# MN42_v2a.net
KiCad netlist of a schematic drawn in EasyEDA Pro
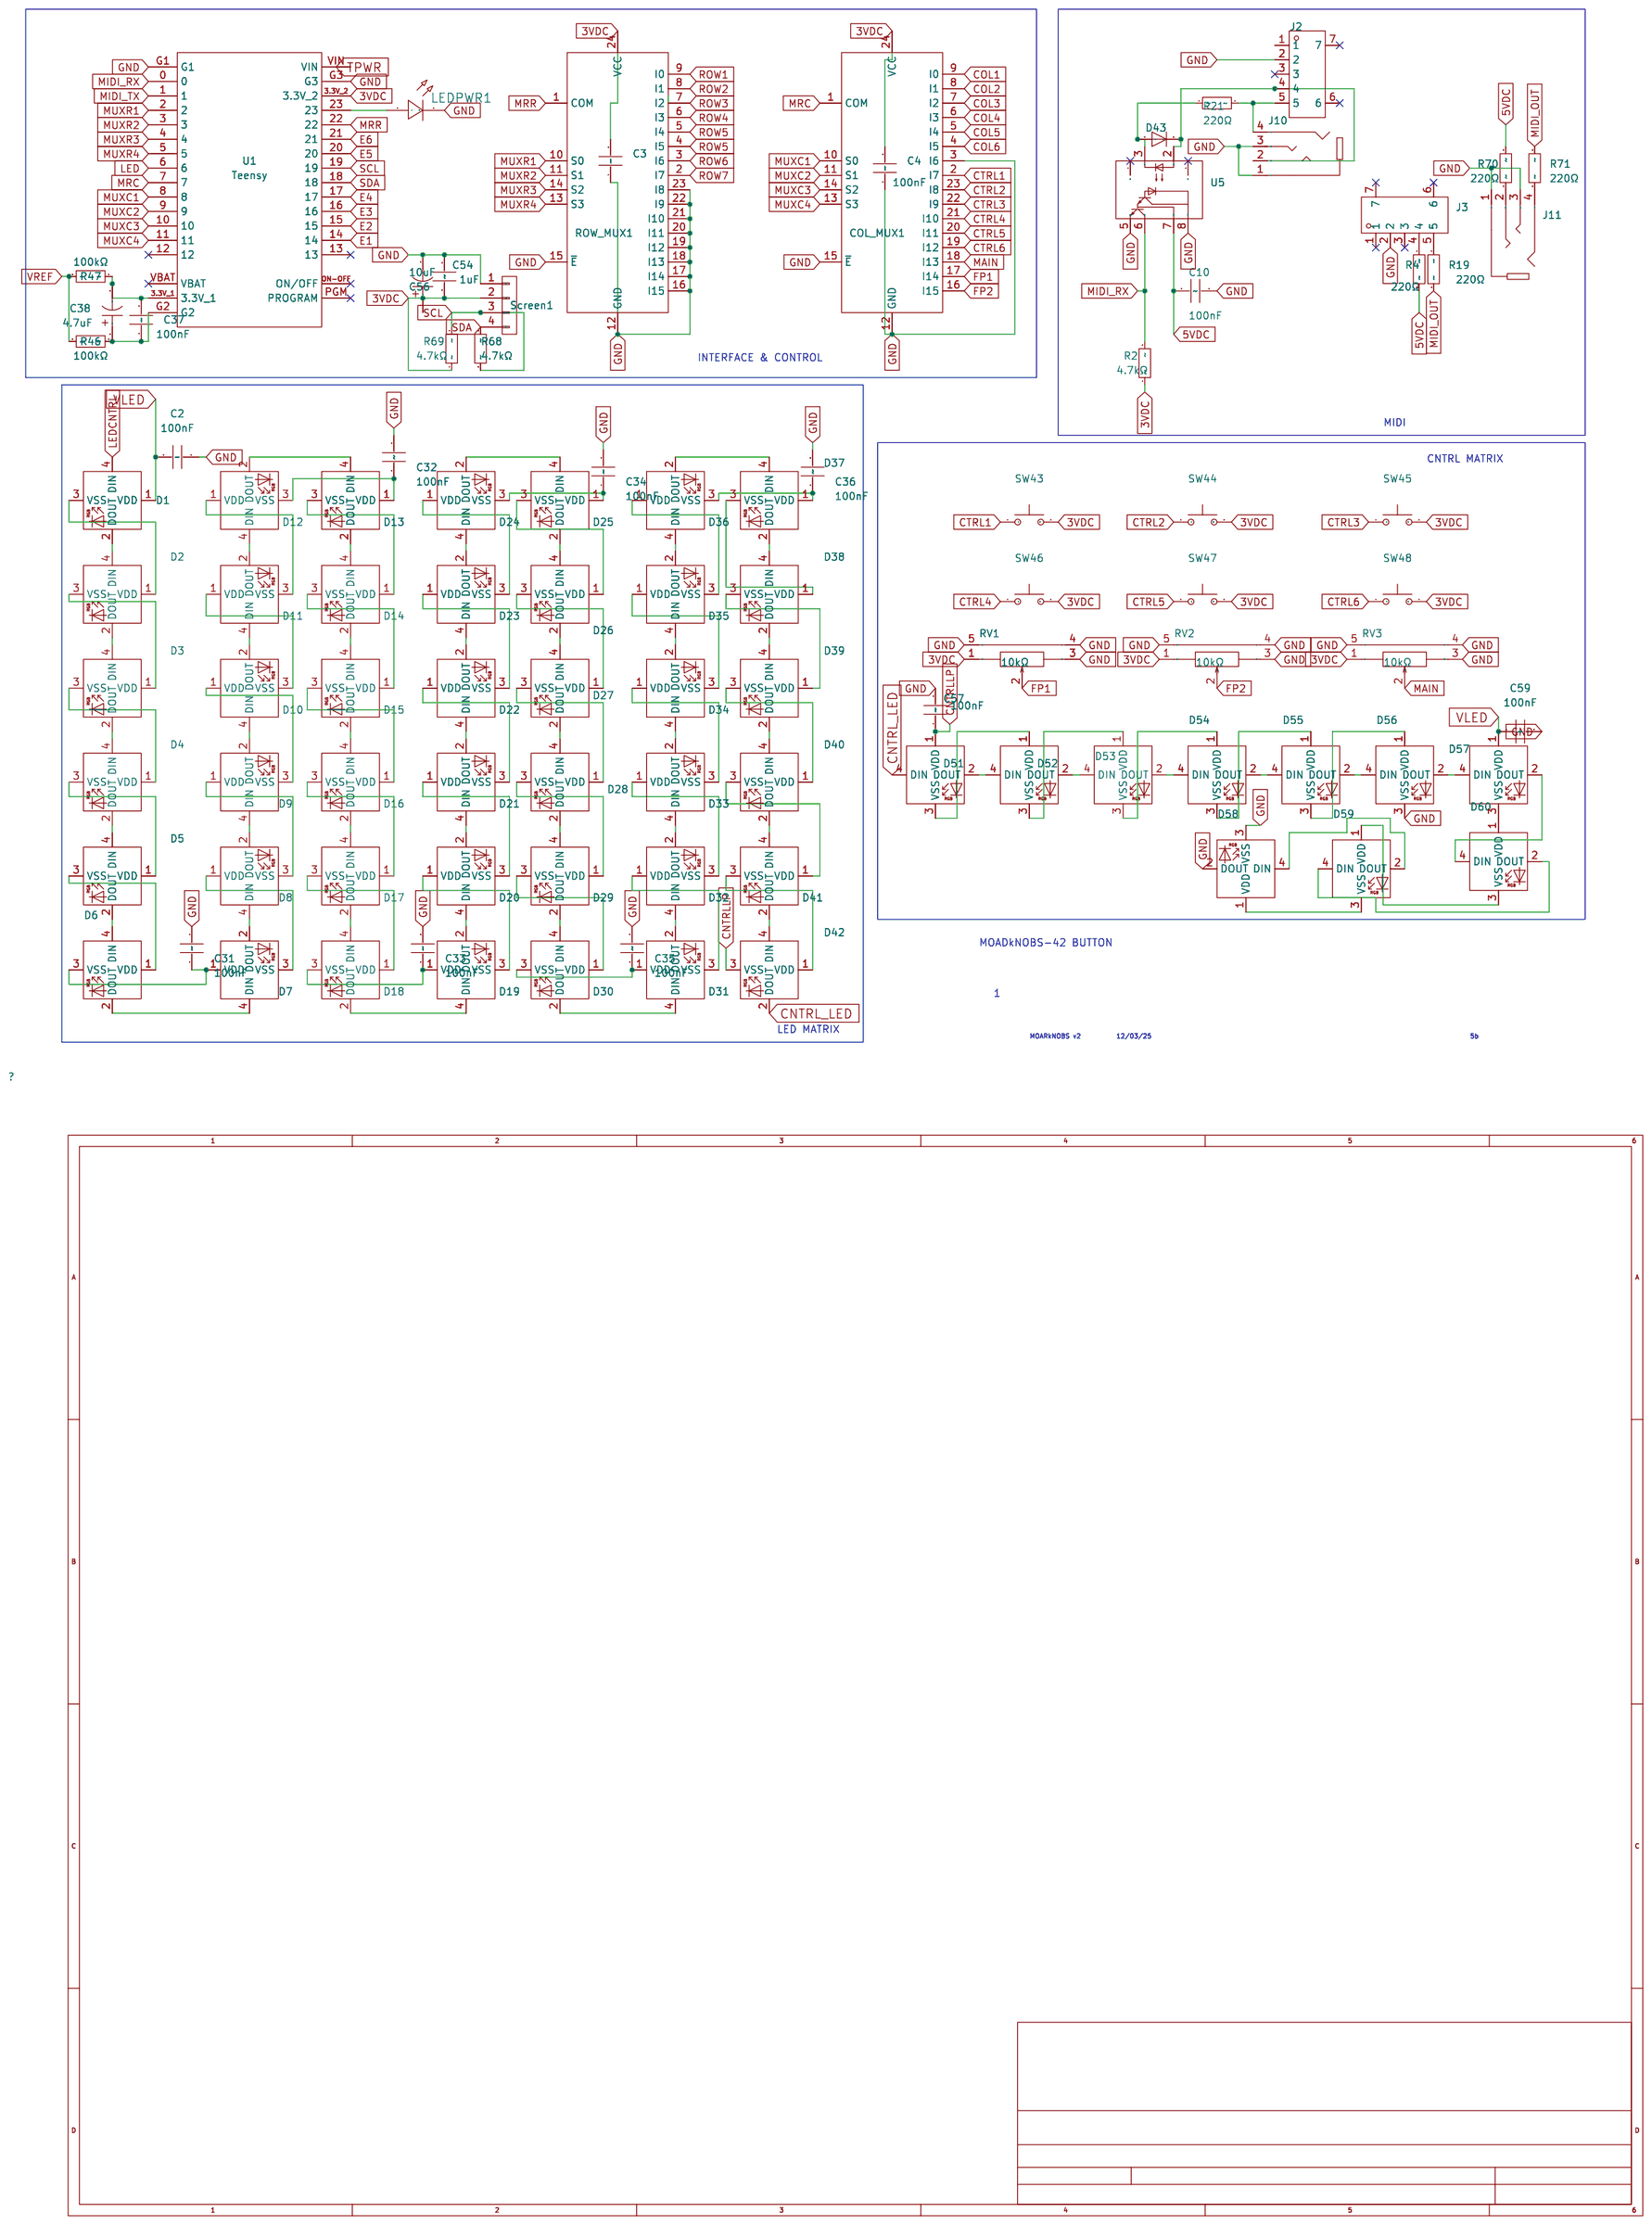
[diagram p0: INTERFACE/LED/MIDI/CNTRL]
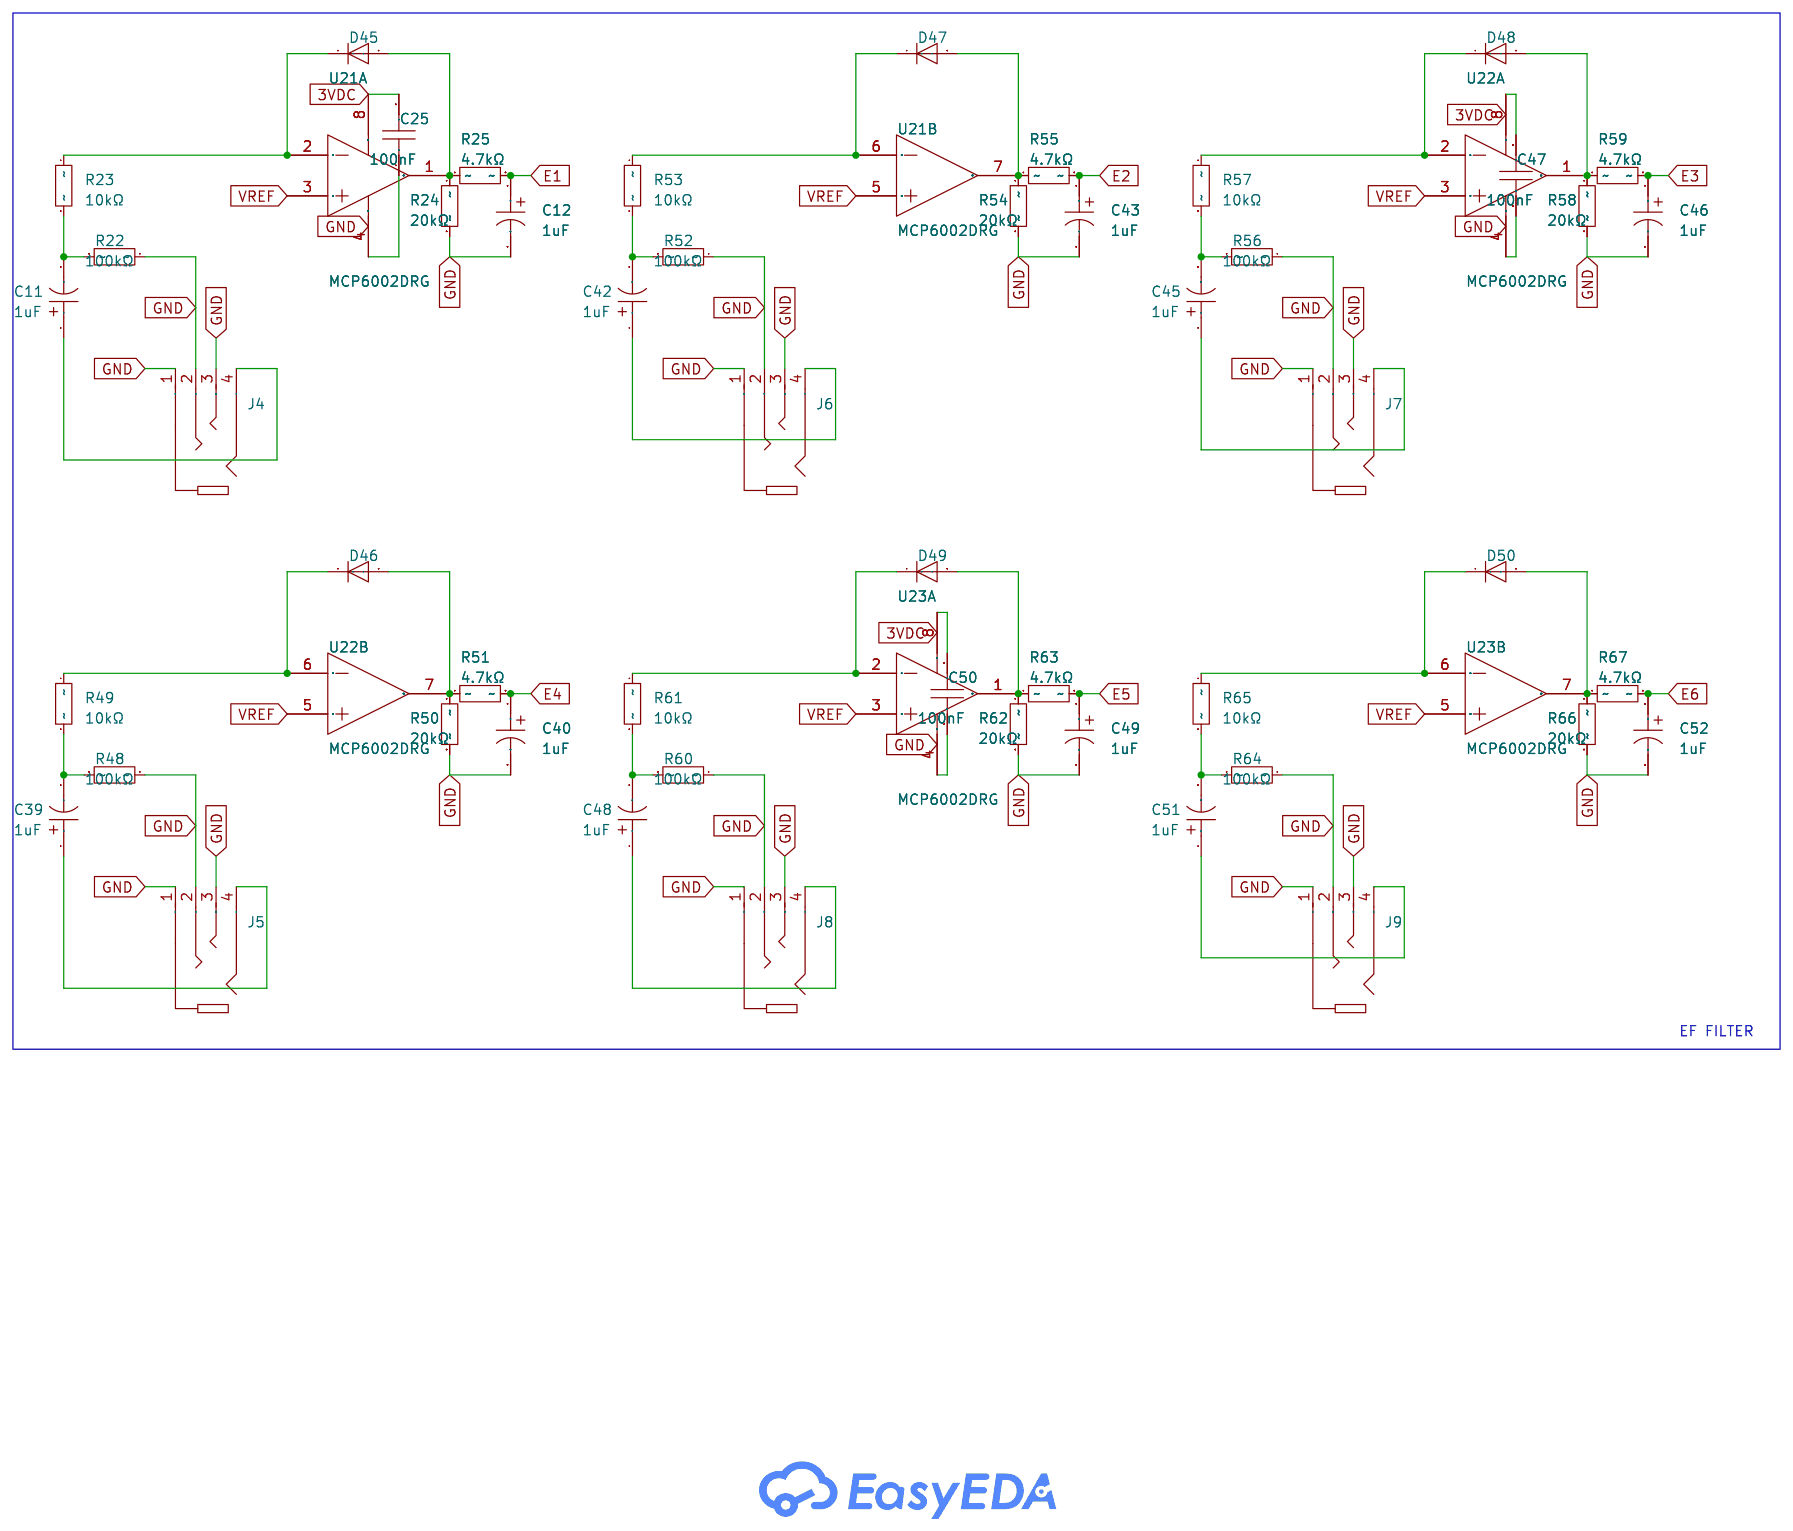
[diagram p1: ENVELOPE]
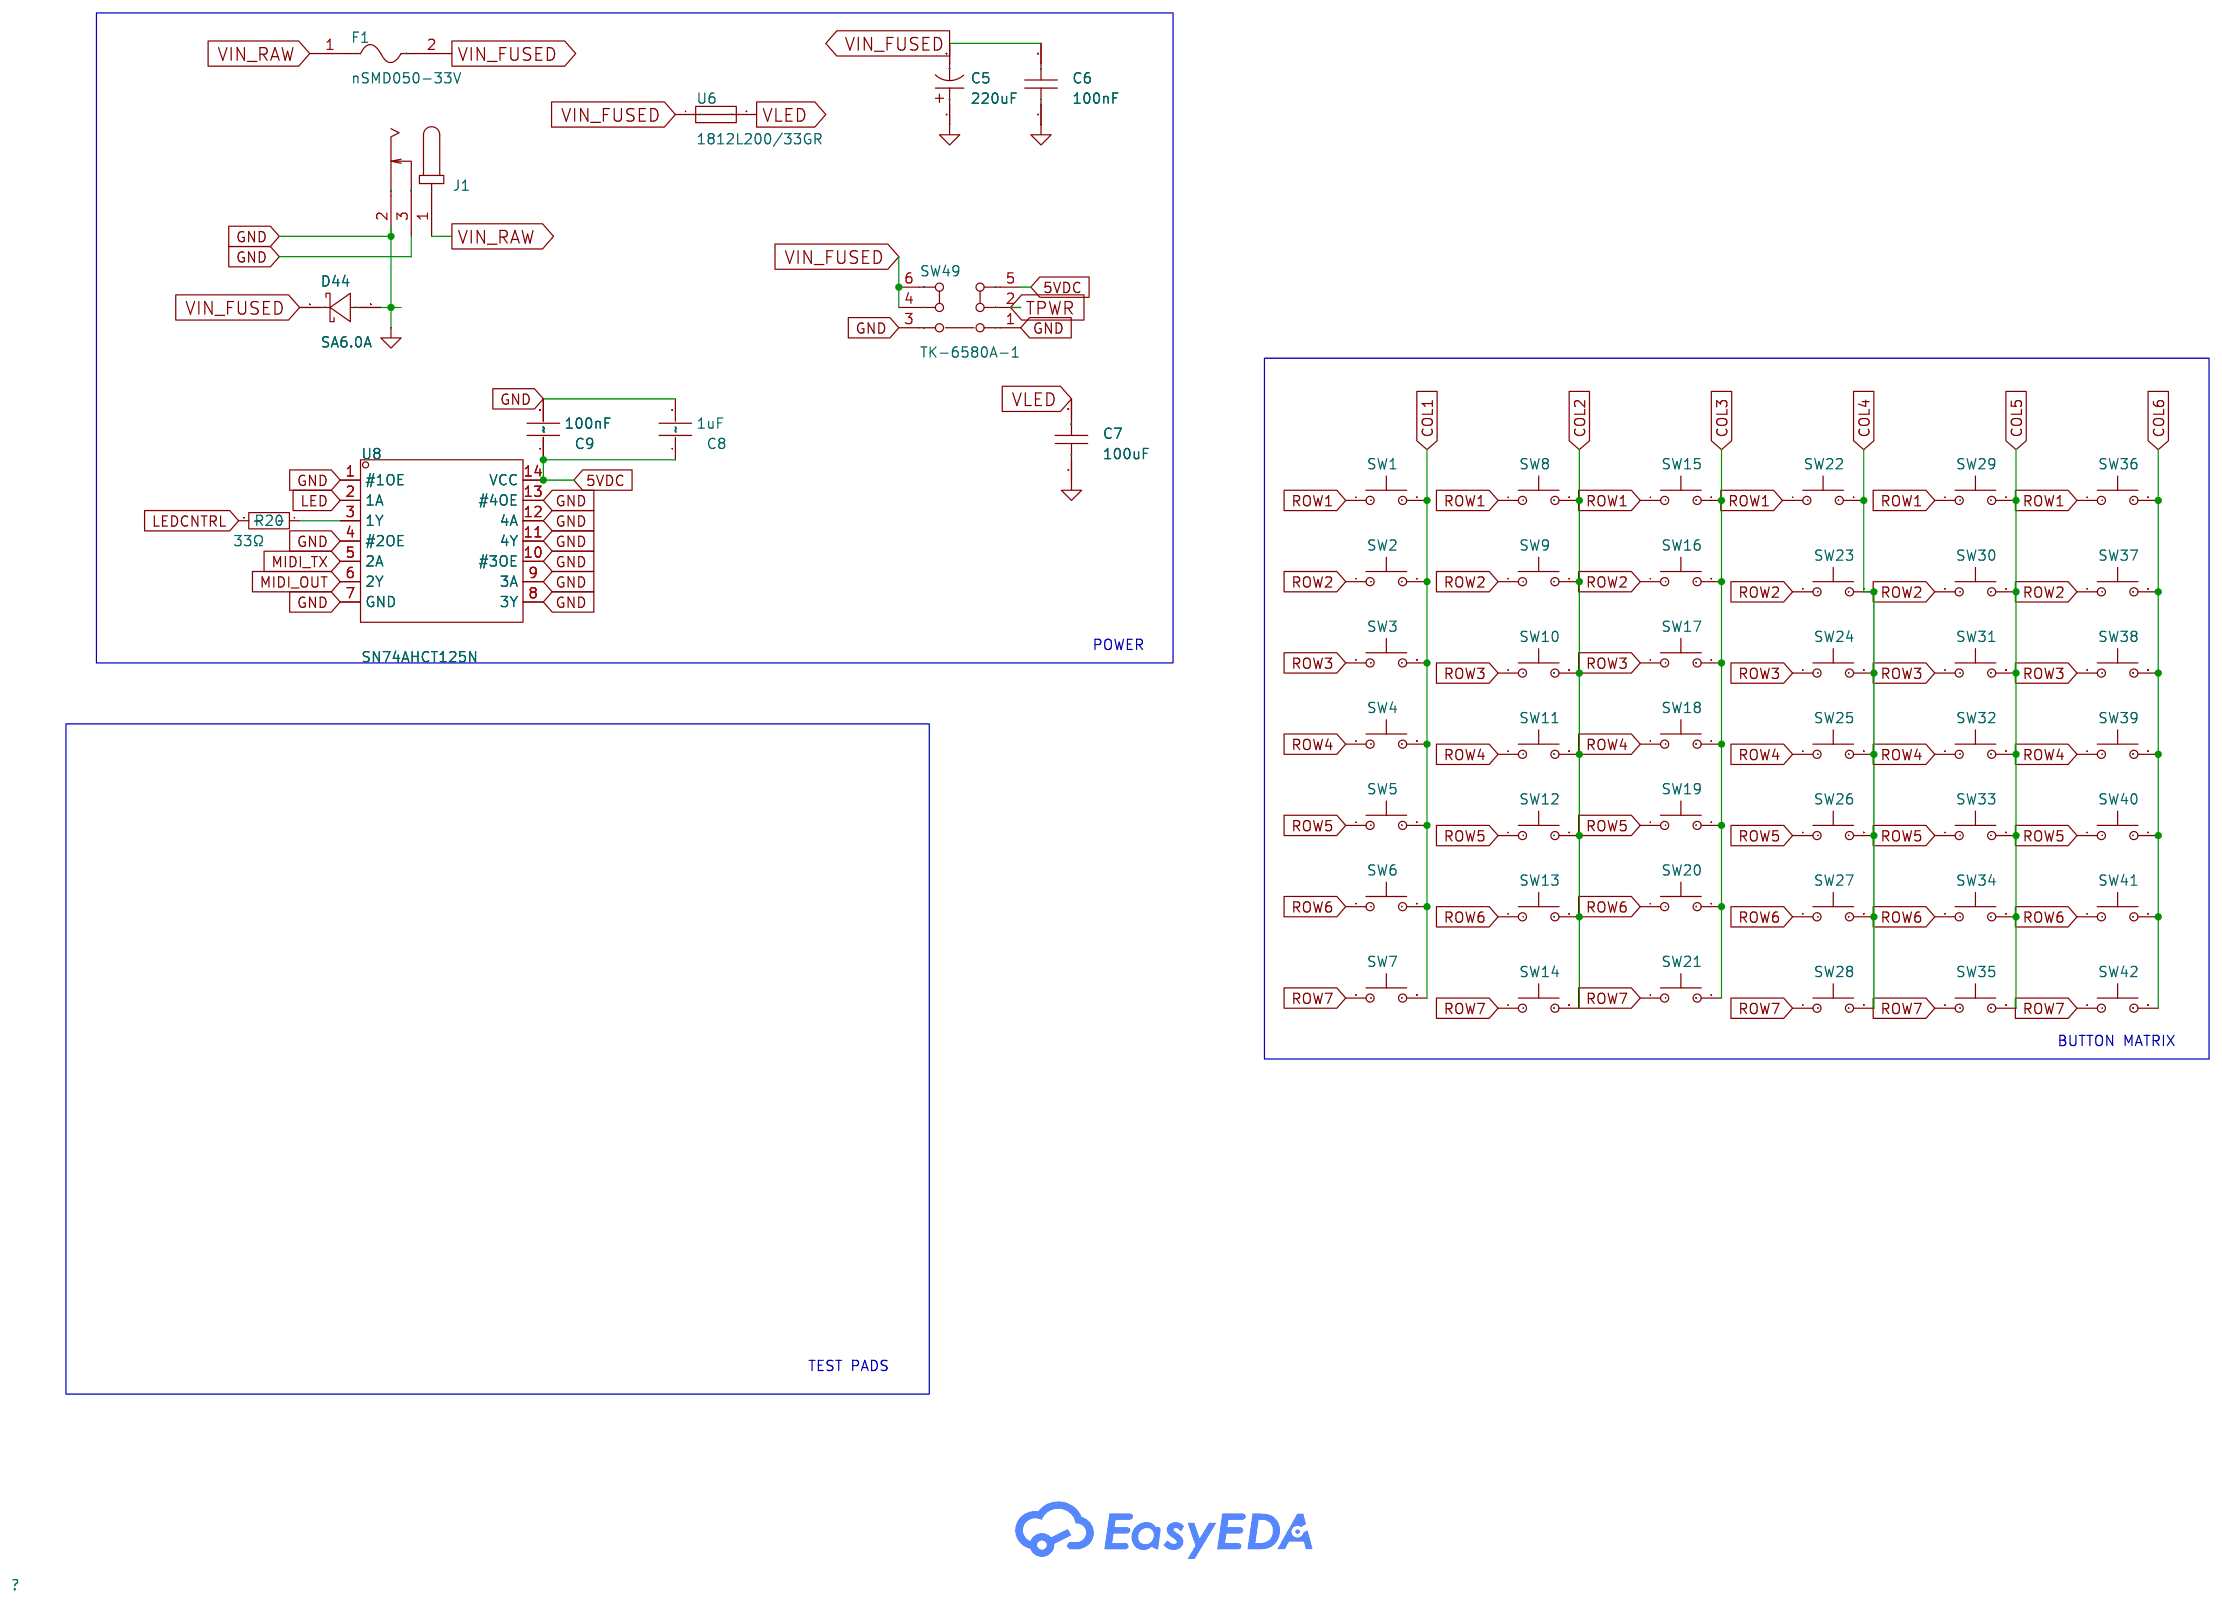
[diagram p2: PWR/BUTTON/TEST]

(export (version "E")
  (design (tool "Eeschema 10.0.6"))
  (components
    (comp (ref "C2")
      (value "100nF")
      (footprint "easyedapro:Capacitor_THT:C_Disc_D3.4mm_W2.1mm_P2.50mm")
      (description "Capacitance:100nF Tolerance:±10% Tolerance:±10% Voltage Rating:63V Temperature Coefficient:-")
      (fields
        (field (name "Manufacturer Part") "CT4G-0805-2X1-63V-0.1μF-K")
        (field (name "Manufacturer") "TORCH(火炬)")
      )
      (libsource (lib "easyedapro") (part "Device_C"))
    )
    (comp (ref "C3")
      (value "100nF")
      (footprint "easyedapro:Capacitor_THT:C_Disc_D3.4mm_W2.1mm_P2.50mm")
      (description "Capacitance:100nF Tolerance:±10% Tolerance:±10% Voltage Rating:63V Temperature Coefficient:-")
      (fields
        (field (name "Manufacturer Part") "CT4G-0805-2X1-63V-0.1μF-K")
        (field (name "Manufacturer") "TORCH(火炬)")
      )
      (libsource (lib "easyedapro") (part "Device_C"))
    )
    (comp (ref "C4")
      (value "100nF")
      (footprint "easyedapro:Capacitor_THT:C_Disc_D3.4mm_W2.1mm_P2.50mm")
      (description "Capacitance:100nF Tolerance:±10% Tolerance:±10% Voltage Rating:63V Temperature Coefficient:-")
      (fields
        (field (name "Manufacturer Part") "CT4G-0805-2X1-63V-0.1μF-K")
        (field (name "Manufacturer") "TORCH(火炬)")
      )
      (libsource (lib "easyedapro") (part "Device_C"))
    )
    (comp (ref "C10")
      (value "100nF")
      (footprint "easyedapro:Capacitor_THT:C_Disc_D3.4mm_W2.1mm_P2.50mm")
      (description "Capacitance:100nF Tolerance:±10% Tolerance:±10% Voltage Rating:63V Temperature Coefficient:-")
      (fields
        (field (name "Manufacturer Part") "CT4G-0805-2X1-63V-0.1μF-K")
        (field (name "Manufacturer") "TORCH(火炬)")
      )
      (libsource (lib "easyedapro") (part "Device_C"))
    )
    (comp (ref "C31")
      (value "100nF")
      (footprint "easyedapro:Capacitor_THT:C_Disc_D3.4mm_W2.1mm_P2.50mm")
      (description "Capacitance:100nF Tolerance:±10% Tolerance:±10% Voltage Rating:63V Temperature Coefficient:-")
      (fields
        (field (name "Manufacturer Part") "CT4G-0805-2X1-63V-0.1μF-K")
        (field (name "Manufacturer") "TORCH(火炬)")
      )
      (libsource (lib "easyedapro") (part "Device_C"))
    )
    (comp (ref "C32")
      (value "100nF")
      (footprint "easyedapro:Capacitor_THT:C_Disc_D3.4mm_W2.1mm_P2.50mm")
      (description "Capacitance:100nF Tolerance:±10% Tolerance:±10% Voltage Rating:63V Temperature Coefficient:-")
      (fields
        (field (name "Manufacturer Part") "CT4G-0805-2X1-63V-0.1μF-K")
        (field (name "Manufacturer") "TORCH(火炬)")
      )
      (libsource (lib "easyedapro") (part "Device_C"))
    )
    (comp (ref "C33")
      (value "100nF")
      (footprint "easyedapro:Capacitor_THT:C_Disc_D3.4mm_W2.1mm_P2.50mm")
      (description "Capacitance:100nF Tolerance:±10% Tolerance:±10% Voltage Rating:63V Temperature Coefficient:-")
      (fields
        (field (name "Manufacturer Part") "CT4G-0805-2X1-63V-0.1μF-K")
        (field (name "Manufacturer") "TORCH(火炬)")
      )
      (libsource (lib "easyedapro") (part "Device_C"))
    )
    (comp (ref "C34")
      (value "100nF")
      (footprint "easyedapro:Capacitor_THT:C_Disc_D3.4mm_W2.1mm_P2.50mm")
      (description "Capacitance:100nF Tolerance:±10% Tolerance:±10% Voltage Rating:63V Temperature Coefficient:-")
      (fields
        (field (name "Manufacturer Part") "CT4G-0805-2X1-63V-0.1μF-K")
        (field (name "Manufacturer") "TORCH(火炬)")
      )
      (libsource (lib "easyedapro") (part "Device_C"))
    )
    (comp (ref "C35")
      (value "100nF")
      (footprint "easyedapro:Capacitor_THT:C_Disc_D3.4mm_W2.1mm_P2.50mm")
      (description "Capacitance:100nF Tolerance:±10% Tolerance:±10% Voltage Rating:63V Temperature Coefficient:-")
      (fields
        (field (name "Manufacturer Part") "CT4G-0805-2X1-63V-0.1μF-K")
        (field (name "Manufacturer") "TORCH(火炬)")
      )
      (libsource (lib "easyedapro") (part "Device_C"))
    )
    (comp (ref "C36")
      (value "100nF")
      (footprint "easyedapro:Capacitor_THT:C_Disc_D3.4mm_W2.1mm_P2.50mm")
      (description "Capacitance:100nF Tolerance:±10% Tolerance:±10% Voltage Rating:63V Temperature Coefficient:-")
      (fields
        (field (name "Manufacturer Part") "CT4G-0805-2X1-63V-0.1μF-K")
        (field (name "Manufacturer") "TORCH(火炬)")
      )
      (libsource (lib "easyedapro") (part "Device_C"))
    )
    (comp (ref "C37")
      (value "100nF")
      (footprint "easyedapro:Capacitor_THT:C_Disc_D3.4mm_W2.1mm_P2.50mm")
      (description "Capacitance:100nF Tolerance:±10% Tolerance:±10% Voltage Rating:63V Temperature Coefficient:-")
      (fields
        (field (name "Manufacturer Part") "CT4G-0805-2X1-63V-0.1μF-K")
        (field (name "Manufacturer") "TORCH(火炬)")
      )
      (libsource (lib "easyedapro") (part "Device_C"))
    )
    (comp (ref "C38")
      (value "4.7uF")
      (footprint "easyedapro:CAP-SMD_BD6.3-L6.6-W6.6-FD")
      (fields (field (name "Manufacturer Part") "189RV0019") (field (name "Manufacturer") "KNSCHA(科尼盛)"))
      (libsource (lib "easyedapro") (part "189RV0019"))
    )
    (comp (ref "C54")
      (value "1uF")
      (footprint "easyedapro:Capacitor_THT:C_Disc_D3.4mm_W2.1mm_P2.50mm")
      (description "Capacitance:100nF Tolerance:±10% Tolerance:±10% Voltage Rating:63V Temperature Coefficient:-")
      (fields
        (field (name "Manufacturer Part") "CT4G-0805-2X1-63V-0.1μF-K")
        (field (name "Manufacturer") "TORCH(火炬)")
      )
      (libsource (lib "easyedapro") (part "Device_C"))
    )
    (comp (ref "C56")
      (value "10uF")
      (footprint "easyedapro:CAP-SMD_BD6.3-L6.6-W6.6-FD")
      (fields (field (name "Manufacturer Part") "189RV0019") (field (name "Manufacturer") "KNSCHA(科尼盛)"))
      (libsource (lib "easyedapro") (part "189RV0019"))
    )
    (comp (ref "C57")
      (value "100nF")
      (footprint "easyedapro:Capacitor_THT:C_Disc_D3.4mm_W2.1mm_P2.50mm")
      (description "Capacitance:100nF Tolerance:±10% Tolerance:±10% Voltage Rating:63V Temperature Coefficient:-")
      (fields
        (field (name "Manufacturer Part") "CT4G-0805-2X1-63V-0.1μF-K")
        (field (name "Manufacturer") "TORCH(火炬)")
      )
      (libsource (lib "easyedapro") (part "Device_C"))
    )
    (comp (ref "C59")
      (value "100nF")
      (footprint "easyedapro:Capacitor_THT:C_Disc_D3.4mm_W2.1mm_P2.50mm")
      (description "Capacitance:100nF Tolerance:±10% Tolerance:±10% Voltage Rating:63V Temperature Coefficient:-")
      (fields
        (field (name "Manufacturer Part") "CT4G-0805-2X1-63V-0.1μF-K")
        (field (name "Manufacturer") "TORCH(火炬)")
      )
      (libsource (lib "easyedapro") (part "Device_C"))
    )
    (comp (ref "COL_MUX1")
      (value "CD74HC4067M96")
      (footprint "easyedapro:Package_SO:SOIC-24W_7.5x15.4mm_P1.27mm")
      (fields (field (name "Manufacturer") "TI(德州仪器)"))
      (libsource (lib "easyedapro") (part "74xx_CD74HC4067M"))
    )
    (comp (ref "D1")
      (value "XL-5050RGBC-WS2812B")
      (footprint "easyedapro:LED_SMD:LED_WS2812B_PLCC4_5.0x5.0mm_P3.2mm")
      (fields (field (name "Manufacturer") "XINGLIGHT(成兴光)"))
      (libsource (lib "easyedapro") (part "LED_WS2812B"))
    )
    (comp (ref "D2")
      (value "XL-5050RGBC-WS2812B")
      (footprint "easyedapro:LED_SMD:LED_WS2812B_PLCC4_5.0x5.0mm_P3.2mm")
      (fields (field (name "Manufacturer") "XINGLIGHT(成兴光)"))
      (libsource (lib "easyedapro") (part "LED_WS2812B"))
    )
    (comp (ref "D3")
      (value "XL-5050RGBC-WS2812B")
      (footprint "easyedapro:LED_SMD:LED_WS2812B_PLCC4_5.0x5.0mm_P3.2mm")
      (fields (field (name "Manufacturer") "XINGLIGHT(成兴光)"))
      (libsource (lib "easyedapro") (part "LED_WS2812B"))
    )
    (comp (ref "D4")
      (value "XL-5050RGBC-WS2812B")
      (footprint "easyedapro:LED_SMD:LED_WS2812B_PLCC4_5.0x5.0mm_P3.2mm")
      (fields (field (name "Manufacturer") "XINGLIGHT(成兴光)"))
      (libsource (lib "easyedapro") (part "LED_WS2812B"))
    )
    (comp (ref "D5")
      (value "XL-5050RGBC-WS2812B")
      (footprint "easyedapro:LED_SMD:LED_WS2812B_PLCC4_5.0x5.0mm_P3.2mm")
      (fields (field (name "Manufacturer") "XINGLIGHT(成兴光)"))
      (libsource (lib "easyedapro") (part "LED_WS2812B"))
    )
    (comp (ref "D6")
      (value "XL-5050RGBC-WS2812B")
      (footprint "easyedapro:LED_SMD:LED_WS2812B_PLCC4_5.0x5.0mm_P3.2mm")
      (fields (field (name "Manufacturer") "XINGLIGHT(成兴光)"))
      (libsource (lib "easyedapro") (part "LED_WS2812B"))
    )
    (comp (ref "D7")
      (value "XL-5050RGBC-WS2812B")
      (footprint "easyedapro:LED_SMD:LED_WS2812B_PLCC4_5.0x5.0mm_P3.2mm")
      (fields (field (name "Manufacturer") "XINGLIGHT(成兴光)"))
      (libsource (lib "easyedapro") (part "LED_WS2812B"))
    )
    (comp (ref "D8")
      (value "XL-5050RGBC-WS2812B")
      (footprint "easyedapro:LED_SMD:LED_WS2812B_PLCC4_5.0x5.0mm_P3.2mm")
      (fields (field (name "Manufacturer") "XINGLIGHT(成兴光)"))
      (libsource (lib "easyedapro") (part "LED_WS2812B"))
    )
    (comp (ref "D9")
      (value "XL-5050RGBC-WS2812B")
      (footprint "easyedapro:LED_SMD:LED_WS2812B_PLCC4_5.0x5.0mm_P3.2mm")
      (fields (field (name "Manufacturer") "XINGLIGHT(成兴光)"))
      (libsource (lib "easyedapro") (part "LED_WS2812B"))
    )
    (comp (ref "D10")
      (value "XL-5050RGBC-WS2812B")
      (footprint "easyedapro:LED_SMD:LED_WS2812B_PLCC4_5.0x5.0mm_P3.2mm")
      (fields (field (name "Manufacturer") "XINGLIGHT(成兴光)"))
      (libsource (lib "easyedapro") (part "LED_WS2812B"))
    )
    (comp (ref "D11")
      (value "XL-5050RGBC-WS2812B")
      (footprint "easyedapro:LED_SMD:LED_WS2812B_PLCC4_5.0x5.0mm_P3.2mm")
      (fields (field (name "Manufacturer") "XINGLIGHT(成兴光)"))
      (libsource (lib "easyedapro") (part "LED_WS2812B"))
    )
    (comp (ref "D12")
      (value "XL-5050RGBC-WS2812B")
      (footprint "easyedapro:LED_SMD:LED_WS2812B_PLCC4_5.0x5.0mm_P3.2mm")
      (fields (field (name "Manufacturer") "XINGLIGHT(成兴光)"))
      (libsource (lib "easyedapro") (part "LED_WS2812B"))
    )
    (comp (ref "D13")
      (value "XL-5050RGBC-WS2812B")
      (footprint "easyedapro:LED_SMD:LED_WS2812B_PLCC4_5.0x5.0mm_P3.2mm")
      (fields (field (name "Manufacturer") "XINGLIGHT(成兴光)"))
      (libsource (lib "easyedapro") (part "LED_WS2812B"))
    )
    (comp (ref "D14")
      (value "XL-5050RGBC-WS2812B")
      (footprint "easyedapro:LED_SMD:LED_WS2812B_PLCC4_5.0x5.0mm_P3.2mm")
      (fields (field (name "Manufacturer") "XINGLIGHT(成兴光)"))
      (libsource (lib "easyedapro") (part "LED_WS2812B"))
    )
    (comp (ref "D15")
      (value "XL-5050RGBC-WS2812B")
      (footprint "easyedapro:LED_SMD:LED_WS2812B_PLCC4_5.0x5.0mm_P3.2mm")
      (fields (field (name "Manufacturer") "XINGLIGHT(成兴光)"))
      (libsource (lib "easyedapro") (part "LED_WS2812B"))
    )
    (comp (ref "D16")
      (value "XL-5050RGBC-WS2812B")
      (footprint "easyedapro:LED_SMD:LED_WS2812B_PLCC4_5.0x5.0mm_P3.2mm")
      (fields (field (name "Manufacturer") "XINGLIGHT(成兴光)"))
      (libsource (lib "easyedapro") (part "LED_WS2812B"))
    )
    (comp (ref "D17")
      (value "XL-5050RGBC-WS2812B")
      (footprint "easyedapro:LED_SMD:LED_WS2812B_PLCC4_5.0x5.0mm_P3.2mm")
      (fields (field (name "Manufacturer") "XINGLIGHT(成兴光)"))
      (libsource (lib "easyedapro") (part "LED_WS2812B"))
    )
    (comp (ref "D18")
      (value "XL-5050RGBC-WS2812B")
      (footprint "easyedapro:LED_SMD:LED_WS2812B_PLCC4_5.0x5.0mm_P3.2mm")
      (fields (field (name "Manufacturer") "XINGLIGHT(成兴光)"))
      (libsource (lib "easyedapro") (part "LED_WS2812B"))
    )
    (comp (ref "D19")
      (value "XL-5050RGBC-WS2812B")
      (footprint "easyedapro:LED_SMD:LED_WS2812B_PLCC4_5.0x5.0mm_P3.2mm")
      (fields (field (name "Manufacturer") "XINGLIGHT(成兴光)"))
      (libsource (lib "easyedapro") (part "LED_WS2812B"))
    )
    (comp (ref "D20")
      (value "XL-5050RGBC-WS2812B")
      (footprint "easyedapro:LED_SMD:LED_WS2812B_PLCC4_5.0x5.0mm_P3.2mm")
      (fields (field (name "Manufacturer") "XINGLIGHT(成兴光)"))
      (libsource (lib "easyedapro") (part "LED_WS2812B"))
    )
    (comp (ref "D21")
      (value "XL-5050RGBC-WS2812B")
      (footprint "easyedapro:LED_SMD:LED_WS2812B_PLCC4_5.0x5.0mm_P3.2mm")
      (fields (field (name "Manufacturer") "XINGLIGHT(成兴光)"))
      (libsource (lib "easyedapro") (part "LED_WS2812B"))
    )
    (comp (ref "D22")
      (value "XL-5050RGBC-WS2812B")
      (footprint "easyedapro:LED_SMD:LED_WS2812B_PLCC4_5.0x5.0mm_P3.2mm")
      (fields (field (name "Manufacturer") "XINGLIGHT(成兴光)"))
      (libsource (lib "easyedapro") (part "LED_WS2812B"))
    )
    (comp (ref "D23")
      (value "XL-5050RGBC-WS2812B")
      (footprint "easyedapro:LED_SMD:LED_WS2812B_PLCC4_5.0x5.0mm_P3.2mm")
      (fields (field (name "Manufacturer") "XINGLIGHT(成兴光)"))
      (libsource (lib "easyedapro") (part "LED_WS2812B"))
    )
    (comp (ref "D24")
      (value "XL-5050RGBC-WS2812B")
      (footprint "easyedapro:LED_SMD:LED_WS2812B_PLCC4_5.0x5.0mm_P3.2mm")
      (fields (field (name "Manufacturer") "XINGLIGHT(成兴光)"))
      (libsource (lib "easyedapro") (part "LED_WS2812B"))
    )
    (comp (ref "D25")
      (value "XL-5050RGBC-WS2812B")
      (footprint "easyedapro:LED_SMD:LED_WS2812B_PLCC4_5.0x5.0mm_P3.2mm")
      (fields (field (name "Manufacturer") "XINGLIGHT(成兴光)"))
      (libsource (lib "easyedapro") (part "LED_WS2812B"))
    )
    (comp (ref "D26")
      (value "XL-5050RGBC-WS2812B")
      (footprint "easyedapro:LED_SMD:LED_WS2812B_PLCC4_5.0x5.0mm_P3.2mm")
      (fields (field (name "Manufacturer") "XINGLIGHT(成兴光)"))
      (libsource (lib "easyedapro") (part "LED_WS2812B"))
    )
    (comp (ref "D27")
      (value "XL-5050RGBC-WS2812B")
      (footprint "easyedapro:LED_SMD:LED_WS2812B_PLCC4_5.0x5.0mm_P3.2mm")
      (fields (field (name "Manufacturer") "XINGLIGHT(成兴光)"))
      (libsource (lib "easyedapro") (part "LED_WS2812B"))
    )
    (comp (ref "D28")
      (value "XL-5050RGBC-WS2812B")
      (footprint "easyedapro:LED_SMD:LED_WS2812B_PLCC4_5.0x5.0mm_P3.2mm")
      (fields (field (name "Manufacturer") "XINGLIGHT(成兴光)"))
      (libsource (lib "easyedapro") (part "LED_WS2812B"))
    )
    (comp (ref "D29")
      (value "XL-5050RGBC-WS2812B")
      (footprint "easyedapro:LED_SMD:LED_WS2812B_PLCC4_5.0x5.0mm_P3.2mm")
      (fields (field (name "Manufacturer") "XINGLIGHT(成兴光)"))
      (libsource (lib "easyedapro") (part "LED_WS2812B"))
    )
    (comp (ref "D30")
      (value "XL-5050RGBC-WS2812B")
      (footprint "easyedapro:LED_SMD:LED_WS2812B_PLCC4_5.0x5.0mm_P3.2mm")
      (fields (field (name "Manufacturer") "XINGLIGHT(成兴光)"))
      (libsource (lib "easyedapro") (part "LED_WS2812B"))
    )
    (comp (ref "D31")
      (value "XL-5050RGBC-WS2812B")
      (footprint "easyedapro:LED_SMD:LED_WS2812B_PLCC4_5.0x5.0mm_P3.2mm")
      (fields (field (name "Manufacturer") "XINGLIGHT(成兴光)"))
      (libsource (lib "easyedapro") (part "LED_WS2812B"))
    )
    (comp (ref "D32")
      (value "XL-5050RGBC-WS2812B")
      (footprint "easyedapro:LED_SMD:LED_WS2812B_PLCC4_5.0x5.0mm_P3.2mm")
      (fields (field (name "Manufacturer") "XINGLIGHT(成兴光)"))
      (libsource (lib "easyedapro") (part "LED_WS2812B"))
    )
    (comp (ref "D33")
      (value "XL-5050RGBC-WS2812B")
      (footprint "easyedapro:LED_SMD:LED_WS2812B_PLCC4_5.0x5.0mm_P3.2mm")
      (fields (field (name "Manufacturer") "XINGLIGHT(成兴光)"))
      (libsource (lib "easyedapro") (part "LED_WS2812B"))
    )
    (comp (ref "D34")
      (value "XL-5050RGBC-WS2812B")
      (footprint "easyedapro:LED_SMD:LED_WS2812B_PLCC4_5.0x5.0mm_P3.2mm")
      (fields (field (name "Manufacturer") "XINGLIGHT(成兴光)"))
      (libsource (lib "easyedapro") (part "LED_WS2812B"))
    )
    (comp (ref "D35")
      (value "XL-5050RGBC-WS2812B")
      (footprint "easyedapro:LED_SMD:LED_WS2812B_PLCC4_5.0x5.0mm_P3.2mm")
      (fields (field (name "Manufacturer") "XINGLIGHT(成兴光)"))
      (libsource (lib "easyedapro") (part "LED_WS2812B"))
    )
    (comp (ref "D36")
      (value "XL-5050RGBC-WS2812B")
      (footprint "easyedapro:LED_SMD:LED_WS2812B_PLCC4_5.0x5.0mm_P3.2mm")
      (fields (field (name "Manufacturer") "XINGLIGHT(成兴光)"))
      (libsource (lib "easyedapro") (part "LED_WS2812B"))
    )
    (comp (ref "D37")
      (value "XL-5050RGBC-WS2812B")
      (footprint "easyedapro:LED_SMD:LED_WS2812B_PLCC4_5.0x5.0mm_P3.2mm")
      (fields (field (name "Manufacturer") "XINGLIGHT(成兴光)"))
      (libsource (lib "easyedapro") (part "LED_WS2812B"))
    )
    (comp (ref "D38")
      (value "XL-5050RGBC-WS2812B")
      (footprint "easyedapro:LED_SMD:LED_WS2812B_PLCC4_5.0x5.0mm_P3.2mm")
      (fields (field (name "Manufacturer") "XINGLIGHT(成兴光)"))
      (libsource (lib "easyedapro") (part "LED_WS2812B"))
    )
    (comp (ref "D39")
      (value "XL-5050RGBC-WS2812B")
      (footprint "easyedapro:LED_SMD:LED_WS2812B_PLCC4_5.0x5.0mm_P3.2mm")
      (fields (field (name "Manufacturer") "XINGLIGHT(成兴光)"))
      (libsource (lib "easyedapro") (part "LED_WS2812B"))
    )
    (comp (ref "D40")
      (value "XL-5050RGBC-WS2812B")
      (footprint "easyedapro:LED_SMD:LED_WS2812B_PLCC4_5.0x5.0mm_P3.2mm")
      (fields (field (name "Manufacturer") "XINGLIGHT(成兴光)"))
      (libsource (lib "easyedapro") (part "LED_WS2812B"))
    )
    (comp (ref "D41")
      (value "XL-5050RGBC-WS2812B")
      (footprint "easyedapro:LED_SMD:LED_WS2812B_PLCC4_5.0x5.0mm_P3.2mm")
      (fields (field (name "Manufacturer") "XINGLIGHT(成兴光)"))
      (libsource (lib "easyedapro") (part "LED_WS2812B"))
    )
    (comp (ref "D42")
      (value "XL-5050RGBC-WS2812B")
      (footprint "easyedapro:LED_SMD:LED_WS2812B_PLCC4_5.0x5.0mm_P3.2mm")
      (fields (field (name "Manufacturer") "XINGLIGHT(成兴光)"))
      (libsource (lib "easyedapro") (part "LED_WS2812B"))
    )
    (comp (ref "D43")
      (value "1N4148PF")
      (footprint "easyedapro:Diode_THT:D_DO-35_SOD27_P7.62mm_Horizontal")
      (fields (field (name "Manufacturer") "ST(先科)"))
      (libsource (lib "easyedapro") (part "Diode_1N4148"))
    )
    (comp (ref "D51")
      (value "XL-5050RGBC-WS2812B")
      (footprint "easyedapro:LED_SMD:LED_WS2812B_PLCC4_5.0x5.0mm_P3.2mm")
      (fields (field (name "Manufacturer") "XINGLIGHT(成兴光)"))
      (libsource (lib "easyedapro") (part "LED_WS2812B"))
    )
    (comp (ref "D52")
      (value "XL-5050RGBC-WS2812B")
      (footprint "easyedapro:LED_SMD:LED_WS2812B_PLCC4_5.0x5.0mm_P3.2mm")
      (fields (field (name "Manufacturer") "XINGLIGHT(成兴光)"))
      (libsource (lib "easyedapro") (part "LED_WS2812B"))
    )
    (comp (ref "D53")
      (value "XL-5050RGBC-WS2812B")
      (footprint "easyedapro:LED_SMD:LED_WS2812B_PLCC4_5.0x5.0mm_P3.2mm")
      (fields (field (name "Manufacturer") "XINGLIGHT(成兴光)"))
      (libsource (lib "easyedapro") (part "LED_WS2812B"))
    )
    (comp (ref "D54")
      (value "XL-5050RGBC-WS2812B")
      (footprint "easyedapro:LED_SMD:LED_WS2812B_PLCC4_5.0x5.0mm_P3.2mm")
      (fields (field (name "Manufacturer") "XINGLIGHT(成兴光)"))
      (libsource (lib "easyedapro") (part "LED_WS2812B"))
    )
    (comp (ref "D55")
      (value "XL-5050RGBC-WS2812B")
      (footprint "easyedapro:LED_SMD:LED_WS2812B_PLCC4_5.0x5.0mm_P3.2mm")
      (fields (field (name "Manufacturer") "XINGLIGHT(成兴光)"))
      (libsource (lib "easyedapro") (part "LED_WS2812B"))
    )
    (comp (ref "D56")
      (value "XL-5050RGBC-WS2812B")
      (footprint "easyedapro:LED_SMD:LED_WS2812B_PLCC4_5.0x5.0mm_P3.2mm")
      (fields (field (name "Manufacturer") "XINGLIGHT(成兴光)"))
      (libsource (lib "easyedapro") (part "LED_WS2812B"))
    )
    (comp (ref "D57")
      (value "XL-5050RGBC-WS2812B")
      (footprint "easyedapro:LED_SMD:LED_WS2812B_PLCC4_5.0x5.0mm_P3.2mm")
      (fields (field (name "Manufacturer") "XINGLIGHT(成兴光)"))
      (libsource (lib "easyedapro") (part "LED_WS2812B"))
    )
    (comp (ref "D58")
      (value "XL-5050RGBC-WS2812B")
      (footprint "easyedapro:LED_SMD:LED_WS2812B_PLCC4_5.0x5.0mm_P3.2mm")
      (fields (field (name "Manufacturer") "XINGLIGHT(成兴光)"))
      (libsource (lib "easyedapro") (part "LED_WS2812B"))
    )
    (comp (ref "D59")
      (value "XL-5050RGBC-WS2812B")
      (footprint "easyedapro:LED_SMD:LED_WS2812B_PLCC4_5.0x5.0mm_P3.2mm")
      (fields (field (name "Manufacturer") "XINGLIGHT(成兴光)"))
      (libsource (lib "easyedapro") (part "LED_WS2812B"))
    )
    (comp (ref "D60")
      (value "XL-5050RGBC-WS2812B")
      (footprint "easyedapro:LED_SMD:LED_WS2812B_PLCC4_5.0x5.0mm_P3.2mm")
      (fields (field (name "Manufacturer") "XINGLIGHT(成兴光)"))
      (libsource (lib "easyedapro") (part "LED_WS2812B"))
    )
    (comp (ref "J2")
      (value "DIN-504B-M10")
      (footprint "easyedapro:CONN-TH_DIN-504B-M10")
      (fields (field (name "Manufacturer") "HOOYA(皓宇电子)"))
      (libsource (lib "easyedapro") (part "DIN-504B-M10"))
    )
    (comp (ref "J3")
      (value "DIN-504B-M10")
      (footprint "easyedapro:CONN-TH_DIN-504B-M10")
      (fields (field (name "Manufacturer") "HOOYA(皓宇电子)"))
      (libsource (lib "easyedapro") (part "DIN-504B-M10"))
    )
    (comp (ref "J10")
      (value "HC-PJ-320A")
      (footprint "easyedapro:AUDIO-SMD_HC-PJ-320A")
      (fields (field (name "Manufacturer") "HC(虹成电子)"))
      (libsource (lib "easyedapro") (part "HC-PJ-320A"))
    )
    (comp (ref "J11")
      (value "HC-PJ-320A")
      (footprint "easyedapro:AUDIO-SMD_HC-PJ-320A")
      (fields (field (name "Manufacturer") "HC(虹成电子)"))
      (libsource (lib "easyedapro") (part "HC-PJ-320A"))
    )
    (comp (ref "LEDPWR1")
      (value "~")
      (footprint "easyedapro:LED_0603")
      (libsource (lib "easyedapro") (part "LED_R"))
    )
    (comp (ref "R2")
      (value "4.7kΩ")
      (footprint "easyedapro:Resistor_THT:R_Axial_DIN0204_L3.6mm_D1.6mm_P2.54mm_Vertical")
      (fields
        (field (name "Manufacturer Part") "RN 1/8W 4K7 F T/B A1")
        (field (name "Manufacturer") "Tyohm(幸亚电阻)")
      )
      (libsource (lib "easyedapro") (part "Device_R"))
    )
    (comp (ref "R4")
      (value "220Ω")
      (footprint "easyedapro:Resistor_THT:R_Axial_DIN0204_L3.6mm_D1.6mm_P2.54mm_Vertical")
      (fields
        (field (name "Manufacturer Part") "RN 1/8W 220R F T/B A1")
        (field (name "Manufacturer") "Tyohm(幸亚电阻)")
      )
      (libsource (lib "easyedapro") (part "Device_R"))
    )
    (comp (ref "R19")
      (value "220Ω")
      (footprint "easyedapro:Resistor_THT:R_Axial_DIN0204_L3.6mm_D1.6mm_P2.54mm_Vertical")
      (fields
        (field (name "Manufacturer Part") "RN 1/8W 220R F T/B A1")
        (field (name "Manufacturer") "Tyohm(幸亚电阻)")
      )
      (libsource (lib "easyedapro") (part "Device_R"))
    )
    (comp (ref "R21")
      (value "220Ω")
      (footprint "easyedapro:Resistor_THT:R_Axial_DIN0204_L3.6mm_D1.6mm_P2.54mm_Vertical")
      (fields
        (field (name "Manufacturer Part") "RN 1/8W 220R F T/B A1")
        (field (name "Manufacturer") "Tyohm(幸亚电阻)")
      )
      (libsource (lib "easyedapro") (part "Device_R"))
    )
    (comp (ref "R46")
      (value "100kΩ")
      (footprint "easyedapro:Resistor_THT:R_Axial_DIN0204_L3.6mm_D1.6mm_P2.54mm_Vertical")
      (fields
        (field (name "Manufacturer Part") "RN1/8W10KFT/BA1")
        (field (name "Manufacturer") "Tyohm(幸亚电阻)")
      )
      (libsource (lib "easyedapro") (part "Device_R"))
    )
    (comp (ref "R47")
      (value "100kΩ")
      (footprint "easyedapro:Resistor_THT:R_Axial_DIN0204_L3.6mm_D1.6mm_P2.54mm_Vertical")
      (fields
        (field (name "Manufacturer Part") "RN1/8W10KFT/BA1")
        (field (name "Manufacturer") "Tyohm(幸亚电阻)")
      )
      (libsource (lib "easyedapro") (part "Device_R"))
    )
    (comp (ref "R68")
      (value "4.7kΩ")
      (footprint "easyedapro:Resistor_THT:R_Axial_DIN0204_L3.6mm_D1.6mm_P2.54mm_Vertical")
      (fields
        (field (name "Manufacturer Part") "RN 1/8W 4K7 F T/B A1")
        (field (name "Manufacturer") "Tyohm(幸亚电阻)")
      )
      (libsource (lib "easyedapro") (part "Device_R"))
    )
    (comp (ref "R69")
      (value "4.7kΩ")
      (footprint "easyedapro:Resistor_THT:R_Axial_DIN0204_L3.6mm_D1.6mm_P2.54mm_Vertical")
      (fields
        (field (name "Manufacturer Part") "RN 1/8W 4K7 F T/B A1")
        (field (name "Manufacturer") "Tyohm(幸亚电阻)")
      )
      (libsource (lib "easyedapro") (part "Device_R"))
    )
    (comp (ref "R70")
      (value "220Ω")
      (footprint "easyedapro:Resistor_THT:R_Axial_DIN0204_L3.6mm_D1.6mm_P2.54mm_Vertical")
      (fields
        (field (name "Manufacturer Part") "RN 1/8W 220R F T/B A1")
        (field (name "Manufacturer") "Tyohm(幸亚电阻)")
      )
      (libsource (lib "easyedapro") (part "Device_R"))
    )
    (comp (ref "R71")
      (value "220Ω")
      (footprint "easyedapro:Resistor_THT:R_Axial_DIN0204_L3.6mm_D1.6mm_P2.54mm_Vertical")
      (fields
        (field (name "Manufacturer Part") "RN 1/8W 220R F T/B A1")
        (field (name "Manufacturer") "Tyohm(幸亚电阻)")
      )
      (libsource (lib "easyedapro") (part "Device_R"))
    )
    (comp (ref "ROW_MUX1")
      (value "CD74HC4067M96")
      (footprint "easyedapro:Package_SO:SOIC-24W_7.5x15.4mm_P1.27mm")
      (fields (field (name "Manufacturer") "TI(德州仪器)"))
      (libsource (lib "easyedapro") (part "74xx_CD74HC4067M"))
    )
    (comp (ref "RV1")
      (value "10kΩ")
      (footprint "easyedapro:RES-ADJ-TH_RK09K1130A5R")
      (description "Resistance: Tolerance:±20% Tolerance:±20%")
      (fields
        (field (name "Manufacturer Part") "RK09K1130A5R")
        (field (name "Manufacturer") "ALPSALPINE(阿尔卑斯阿尔派)")
      )
      (libsource (lib "easyedapro") (part "RK09K1130A5R"))
    )
    (comp (ref "RV2")
      (value "10kΩ")
      (footprint "easyedapro:RES-ADJ-TH_RK09K1130A5R")
      (description "Resistance: Tolerance:±20% Tolerance:±20%")
      (fields
        (field (name "Manufacturer Part") "RK09K1130A5R")
        (field (name "Manufacturer") "ALPSALPINE(阿尔卑斯阿尔派)")
      )
      (libsource (lib "easyedapro") (part "RK09K1130A5R"))
    )
    (comp (ref "RV3")
      (value "10kΩ")
      (footprint "easyedapro:RES-ADJ-TH_RK09K1130A5R")
      (description "Resistance: Tolerance:±20% Tolerance:±20%")
      (fields
        (field (name "Manufacturer Part") "RK09K1130A5R")
        (field (name "Manufacturer") "ALPSALPINE(阿尔卑斯阿尔派)")
      )
      (libsource (lib "easyedapro") (part "RK09K1130A5R"))
    )
    (comp (ref "Screen1")
      (value "HS96L03W2C03")
      (footprint "easyedapro:Connector_JST:JST_EH_S4B-EH_1x04_P2.50mm_Horizontal")
      (fields (field (name "Manufacturer") "HS(汉昇)"))
      (libsource (lib "easyedapro") (part "Connector_Generic_Conn_01x04"))
    )
    (comp (ref "SW43")
      (value "HX B3F-4055-Y")
      (footprint "easyedapro:Button_Switch_SMD:SW_SPST_PTS645")
      (fields (field (name "Manufacturer") "hanxia(韩下)"))
      (libsource (lib "easyedapro") (part "Switch_SW_Push"))
    )
    (comp (ref "SW44")
      (value "HX B3F-4055-Y")
      (footprint "easyedapro:Button_Switch_SMD:SW_SPST_PTS645")
      (fields (field (name "Manufacturer") "hanxia(韩下)"))
      (libsource (lib "easyedapro") (part "Switch_SW_Push"))
    )
    (comp (ref "SW45")
      (value "HX B3F-4055-Y")
      (footprint "easyedapro:Button_Switch_SMD:SW_SPST_PTS645")
      (fields (field (name "Manufacturer") "hanxia(韩下)"))
      (libsource (lib "easyedapro") (part "Switch_SW_Push"))
    )
    (comp (ref "SW46")
      (value "HX B3F-4055-Y")
      (footprint "easyedapro:Button_Switch_SMD:SW_SPST_PTS645")
      (fields (field (name "Manufacturer") "hanxia(韩下)"))
      (libsource (lib "easyedapro") (part "Switch_SW_Push"))
    )
    (comp (ref "SW47")
      (value "HX B3F-4055-Y")
      (footprint "easyedapro:Button_Switch_SMD:SW_SPST_PTS645")
      (fields (field (name "Manufacturer") "hanxia(韩下)"))
      (libsource (lib "easyedapro") (part "Switch_SW_Push"))
    )
    (comp (ref "SW48")
      (value "HX B3F-4055-Y")
      (footprint "easyedapro:Button_Switch_SMD:SW_SPST_PTS645")
      (fields (field (name "Manufacturer") "hanxia(韩下)"))
      (libsource (lib "easyedapro") (part "Switch_SW_Push"))
    )
    (comp (ref "U1")
      (value "Teensy")
      (footprint "easyedapro:teensy 4.0:MODULE_DEV-15583")
      (libsource (lib "easyedapro") (part "teensy40_DEV-15583"))
    )
    (comp (ref "U5")
      (value "6N138")
      (footprint "easyedapro:Package_DIP:DIP-8_W7.62mm")
      (fields (field (name "Manufacturer") "ISOCOM(英国安数光)"))
      (libsource (lib "easyedapro") (part "Isolator_6N138"))
    )
    (comp (ref "C11")
      (value "1uF")
      (footprint "easyedapro:CAP-SMD_BD6.3-L6.6-W6.6-FD")
      (fields (field (name "Manufacturer Part") "189RV0019") (field (name "Manufacturer") "KNSCHA(科尼盛)"))
      (libsource (lib "easyedapro") (part "189RV0019"))
    )
    (comp (ref "C12")
      (value "1uF")
      (footprint "easyedapro:CAP-SMD_BD6.3-L6.6-W6.6-FD")
      (fields (field (name "Manufacturer Part") "189RV0019") (field (name "Manufacturer") "KNSCHA(科尼盛)"))
      (libsource (lib "easyedapro") (part "189RV0019"))
    )
    (comp (ref "C25")
      (value "100nF")
      (footprint "easyedapro:CAP-TH_L5.0-W2.5-P5.00-D1.0")
      (fields
        (field (name "Manufacturer Part") "CC1H104MC1FD3F6C10MF")
        (field (name "Manufacturer") "Dersonic(德尔创)")
      )
      (libsource (lib "easyedapro") (part "CC1H104MC1FD3F6C10MF"))
    )
    (comp (ref "C39")
      (value "1uF")
      (footprint "easyedapro:CAP-SMD_BD6.3-L6.6-W6.6-FD")
      (fields (field (name "Manufacturer Part") "189RV0019") (field (name "Manufacturer") "KNSCHA(科尼盛)"))
      (libsource (lib "easyedapro") (part "189RV0019"))
    )
    (comp (ref "C40")
      (value "1uF")
      (footprint "easyedapro:CAP-SMD_BD6.3-L6.6-W6.6-FD")
      (fields (field (name "Manufacturer Part") "189RV0019") (field (name "Manufacturer") "KNSCHA(科尼盛)"))
      (libsource (lib "easyedapro") (part "189RV0019"))
    )
    (comp (ref "C42")
      (value "1uF")
      (footprint "easyedapro:CAP-SMD_BD6.3-L6.6-W6.6-FD")
      (fields (field (name "Manufacturer Part") "189RV0019") (field (name "Manufacturer") "KNSCHA(科尼盛)"))
      (libsource (lib "easyedapro") (part "189RV0019"))
    )
    (comp (ref "C43")
      (value "1uF")
      (footprint "easyedapro:CAP-SMD_BD6.3-L6.6-W6.6-FD")
      (fields (field (name "Manufacturer Part") "189RV0019") (field (name "Manufacturer") "KNSCHA(科尼盛)"))
      (libsource (lib "easyedapro") (part "189RV0019"))
    )
    (comp (ref "C45")
      (value "1uF")
      (footprint "easyedapro:CAP-SMD_BD6.3-L6.6-W6.6-FD")
      (fields (field (name "Manufacturer Part") "189RV0019") (field (name "Manufacturer") "KNSCHA(科尼盛)"))
      (libsource (lib "easyedapro") (part "189RV0019"))
    )
    (comp (ref "C46")
      (value "1uF")
      (footprint "easyedapro:CAP-SMD_BD6.3-L6.6-W6.6-FD")
      (fields (field (name "Manufacturer Part") "189RV0019") (field (name "Manufacturer") "KNSCHA(科尼盛)"))
      (libsource (lib "easyedapro") (part "189RV0019"))
    )
    (comp (ref "C47")
      (value "100nF")
      (footprint "easyedapro:CAP-TH_L5.0-W2.5-P5.00-D1.0")
      (fields
        (field (name "Manufacturer Part") "CC1H104MC1FD3F6C10MF")
        (field (name "Manufacturer") "Dersonic(德尔创)")
      )
      (libsource (lib "easyedapro") (part "CC1H104MC1FD3F6C10MF"))
    )
    (comp (ref "C48")
      (value "1uF")
      (footprint "easyedapro:CAP-SMD_BD6.3-L6.6-W6.6-FD")
      (fields (field (name "Manufacturer Part") "189RV0019") (field (name "Manufacturer") "KNSCHA(科尼盛)"))
      (libsource (lib "easyedapro") (part "189RV0019"))
    )
    (comp (ref "C49")
      (value "1uF")
      (footprint "easyedapro:CAP-SMD_BD6.3-L6.6-W6.6-FD")
      (fields (field (name "Manufacturer Part") "189RV0019") (field (name "Manufacturer") "KNSCHA(科尼盛)"))
      (libsource (lib "easyedapro") (part "189RV0019"))
    )
    (comp (ref "C50")
      (value "100nF")
      (footprint "easyedapro:CAP-TH_L5.0-W2.5-P5.00-D1.0")
      (fields
        (field (name "Manufacturer Part") "CC1H104MC1FD3F6C10MF")
        (field (name "Manufacturer") "Dersonic(德尔创)")
      )
      (libsource (lib "easyedapro") (part "CC1H104MC1FD3F6C10MF"))
    )
    (comp (ref "C51")
      (value "1uF")
      (footprint "easyedapro:CAP-SMD_BD6.3-L6.6-W6.6-FD")
      (fields (field (name "Manufacturer Part") "189RV0019") (field (name "Manufacturer") "KNSCHA(科尼盛)"))
      (libsource (lib "easyedapro") (part "189RV0019"))
    )
    (comp (ref "C52")
      (value "1uF")
      (footprint "easyedapro:CAP-SMD_BD6.3-L6.6-W6.6-FD")
      (fields (field (name "Manufacturer Part") "189RV0019") (field (name "Manufacturer") "KNSCHA(科尼盛)"))
      (libsource (lib "easyedapro") (part "189RV0019"))
    )
    (comp (ref "D45")
      (value "1N4148PF")
      (footprint "easyedapro:Diode_THT:D_DO-35_SOD27_P7.62mm_Horizontal")
      (fields (field (name "Manufacturer") "ST(先科)"))
      (libsource (lib "easyedapro") (part "Diode_1N4148"))
    )
    (comp (ref "D46")
      (value "1N4148PF")
      (footprint "easyedapro:Diode_THT:D_DO-35_SOD27_P7.62mm_Horizontal")
      (fields (field (name "Manufacturer") "ST(先科)"))
      (libsource (lib "easyedapro") (part "Diode_1N4148"))
    )
    (comp (ref "D47")
      (value "1N4148PF")
      (footprint "easyedapro:Diode_THT:D_DO-35_SOD27_P7.62mm_Horizontal")
      (fields (field (name "Manufacturer") "ST(先科)"))
      (libsource (lib "easyedapro") (part "Diode_1N4148"))
    )
    (comp (ref "D48")
      (value "1N4148PF")
      (footprint "easyedapro:Diode_THT:D_DO-35_SOD27_P7.62mm_Horizontal")
      (fields (field (name "Manufacturer") "ST(先科)"))
      (libsource (lib "easyedapro") (part "Diode_1N4148"))
    )
    (comp (ref "D49")
      (value "1N4148PF")
      (footprint "easyedapro:Diode_THT:D_DO-35_SOD27_P7.62mm_Horizontal")
      (fields (field (name "Manufacturer") "ST(先科)"))
      (libsource (lib "easyedapro") (part "Diode_1N4148"))
    )
    (comp (ref "D50")
      (value "1N4148PF")
      (footprint "easyedapro:Diode_THT:D_DO-35_SOD27_P7.62mm_Horizontal")
      (fields (field (name "Manufacturer") "ST(先科)"))
      (libsource (lib "easyedapro") (part "Diode_1N4148"))
    )
    (comp (ref "J4")
      (value "HC-PJ-320A")
      (footprint "easyedapro:AUDIO-SMD_HC-PJ-320A")
      (fields (field (name "Manufacturer") "HC(虹成电子)"))
      (libsource (lib "easyedapro") (part "HC-PJ-320A"))
    )
    (comp (ref "J5")
      (value "HC-PJ-320A")
      (footprint "easyedapro:AUDIO-SMD_HC-PJ-320A")
      (fields (field (name "Manufacturer") "HC(虹成电子)"))
      (libsource (lib "easyedapro") (part "HC-PJ-320A"))
    )
    (comp (ref "J6")
      (value "HC-PJ-320A")
      (footprint "easyedapro:AUDIO-SMD_HC-PJ-320A")
      (fields (field (name "Manufacturer") "HC(虹成电子)"))
      (libsource (lib "easyedapro") (part "HC-PJ-320A"))
    )
    (comp (ref "J7")
      (value "HC-PJ-320A")
      (footprint "easyedapro:AUDIO-SMD_HC-PJ-320A")
      (fields (field (name "Manufacturer") "HC(虹成电子)"))
      (libsource (lib "easyedapro") (part "HC-PJ-320A"))
    )
    (comp (ref "J8")
      (value "HC-PJ-320A")
      (footprint "easyedapro:AUDIO-SMD_HC-PJ-320A")
      (fields (field (name "Manufacturer") "HC(虹成电子)"))
      (libsource (lib "easyedapro") (part "HC-PJ-320A"))
    )
    (comp (ref "J9")
      (value "HC-PJ-320A")
      (footprint "easyedapro:AUDIO-SMD_HC-PJ-320A")
      (fields (field (name "Manufacturer") "HC(虹成电子)"))
      (libsource (lib "easyedapro") (part "HC-PJ-320A"))
    )
    (comp (ref "R22")
      (value "100kΩ")
      (footprint "easyedapro:Resistor_THT:R_Axial_DIN0204_L3.6mm_D1.6mm_P2.54mm_Vertical")
      (fields
        (field (name "Manufacturer Part") "RN 1/8W 4K7 F T/B A1")
        (field (name "Manufacturer") "Tyohm(幸亚电阻)")
      )
      (libsource (lib "easyedapro") (part "Device_R"))
    )
    (comp (ref "R23")
      (value "10kΩ")
      (footprint "easyedapro:Resistor_THT:R_Axial_DIN0204_L3.6mm_D1.6mm_P2.54mm_Vertical")
      (fields
        (field (name "Manufacturer Part") "RN 1/8W 4K7 F T/B A1")
        (field (name "Manufacturer") "Tyohm(幸亚电阻)")
      )
      (libsource (lib "easyedapro") (part "Device_R"))
    )
    (comp (ref "R24")
      (value "20kΩ")
      (footprint "easyedapro:Resistor_THT:R_Axial_DIN0204_L3.6mm_D1.6mm_P2.54mm_Vertical")
      (fields
        (field (name "Manufacturer Part") "RN 1/8W 4K7 F T/B A1")
        (field (name "Manufacturer") "Tyohm(幸亚电阻)")
      )
      (libsource (lib "easyedapro") (part "Device_R"))
    )
    (comp (ref "R25")
      (value "4.7kΩ")
      (footprint "easyedapro:Resistor_THT:R_Axial_DIN0204_L3.6mm_D1.6mm_P2.54mm_Vertical")
      (fields
        (field (name "Manufacturer Part") "RN 1/8W 4K7 F T/B A1")
        (field (name "Manufacturer") "Tyohm(幸亚电阻)")
      )
      (libsource (lib "easyedapro") (part "Device_R"))
    )
    (comp (ref "R48")
      (value "100kΩ")
      (footprint "easyedapro:Resistor_THT:R_Axial_DIN0204_L3.6mm_D1.6mm_P2.54mm_Vertical")
      (fields
        (field (name "Manufacturer Part") "RN 1/8W 4K7 F T/B A1")
        (field (name "Manufacturer") "Tyohm(幸亚电阻)")
      )
      (libsource (lib "easyedapro") (part "Device_R"))
    )
    (comp (ref "R49")
      (value "10kΩ")
      (footprint "easyedapro:Resistor_THT:R_Axial_DIN0204_L3.6mm_D1.6mm_P2.54mm_Vertical")
      (fields
        (field (name "Manufacturer Part") "RN 1/8W 4K7 F T/B A1")
        (field (name "Manufacturer") "Tyohm(幸亚电阻)")
      )
      (libsource (lib "easyedapro") (part "Device_R"))
    )
    (comp (ref "R50")
      (value "20kΩ")
      (footprint "easyedapro:Resistor_THT:R_Axial_DIN0204_L3.6mm_D1.6mm_P2.54mm_Vertical")
      (fields
        (field (name "Manufacturer Part") "RN 1/8W 4K7 F T/B A1")
        (field (name "Manufacturer") "Tyohm(幸亚电阻)")
      )
      (libsource (lib "easyedapro") (part "Device_R"))
    )
    (comp (ref "R51")
      (value "4.7kΩ")
      (footprint "easyedapro:Resistor_THT:R_Axial_DIN0204_L3.6mm_D1.6mm_P2.54mm_Vertical")
      (fields
        (field (name "Manufacturer Part") "RN 1/8W 4K7 F T/B A1")
        (field (name "Manufacturer") "Tyohm(幸亚电阻)")
      )
      (libsource (lib "easyedapro") (part "Device_R"))
    )
    (comp (ref "R52")
      (value "100kΩ")
      (footprint "easyedapro:Resistor_THT:R_Axial_DIN0204_L3.6mm_D1.6mm_P2.54mm_Vertical")
      (fields
        (field (name "Manufacturer Part") "RN 1/8W 4K7 F T/B A1")
        (field (name "Manufacturer") "Tyohm(幸亚电阻)")
      )
      (libsource (lib "easyedapro") (part "Device_R"))
    )
    (comp (ref "R53")
      (value "10kΩ")
      (footprint "easyedapro:Resistor_THT:R_Axial_DIN0204_L3.6mm_D1.6mm_P2.54mm_Vertical")
      (fields
        (field (name "Manufacturer Part") "RN 1/8W 4K7 F T/B A1")
        (field (name "Manufacturer") "Tyohm(幸亚电阻)")
      )
      (libsource (lib "easyedapro") (part "Device_R"))
    )
    (comp (ref "R54")
      (value "20kΩ")
      (footprint "easyedapro:Resistor_THT:R_Axial_DIN0204_L3.6mm_D1.6mm_P2.54mm_Vertical")
      (fields
        (field (name "Manufacturer Part") "RN 1/8W 4K7 F T/B A1")
        (field (name "Manufacturer") "Tyohm(幸亚电阻)")
      )
      (libsource (lib "easyedapro") (part "Device_R"))
    )
    (comp (ref "R55")
      (value "4.7kΩ")
      (footprint "easyedapro:Resistor_THT:R_Axial_DIN0204_L3.6mm_D1.6mm_P2.54mm_Vertical")
      (fields
        (field (name "Manufacturer Part") "RN 1/8W 4K7 F T/B A1")
        (field (name "Manufacturer") "Tyohm(幸亚电阻)")
      )
      (libsource (lib "easyedapro") (part "Device_R"))
    )
    (comp (ref "R56")
      (value "100kΩ")
      (footprint "easyedapro:Resistor_THT:R_Axial_DIN0204_L3.6mm_D1.6mm_P2.54mm_Vertical")
      (fields
        (field (name "Manufacturer Part") "RN 1/8W 4K7 F T/B A1")
        (field (name "Manufacturer") "Tyohm(幸亚电阻)")
      )
      (libsource (lib "easyedapro") (part "Device_R"))
    )
    (comp (ref "R57")
      (value "10kΩ")
      (footprint "easyedapro:Resistor_THT:R_Axial_DIN0204_L3.6mm_D1.6mm_P2.54mm_Vertical")
      (fields
        (field (name "Manufacturer Part") "RN 1/8W 4K7 F T/B A1")
        (field (name "Manufacturer") "Tyohm(幸亚电阻)")
      )
      (libsource (lib "easyedapro") (part "Device_R"))
    )
    (comp (ref "R58")
      (value "20kΩ")
      (footprint "easyedapro:Resistor_THT:R_Axial_DIN0204_L3.6mm_D1.6mm_P2.54mm_Vertical")
      (fields
        (field (name "Manufacturer Part") "RN 1/8W 4K7 F T/B A1")
        (field (name "Manufacturer") "Tyohm(幸亚电阻)")
      )
      (libsource (lib "easyedapro") (part "Device_R"))
    )
    (comp (ref "R59")
      (value "4.7kΩ")
      (footprint "easyedapro:Resistor_THT:R_Axial_DIN0204_L3.6mm_D1.6mm_P2.54mm_Vertical")
      (fields
        (field (name "Manufacturer Part") "RN 1/8W 4K7 F T/B A1")
        (field (name "Manufacturer") "Tyohm(幸亚电阻)")
      )
      (libsource (lib "easyedapro") (part "Device_R"))
    )
    (comp (ref "R60")
      (value "100kΩ")
      (footprint "easyedapro:Resistor_THT:R_Axial_DIN0204_L3.6mm_D1.6mm_P2.54mm_Vertical")
      (fields
        (field (name "Manufacturer Part") "RN 1/8W 4K7 F T/B A1")
        (field (name "Manufacturer") "Tyohm(幸亚电阻)")
      )
      (libsource (lib "easyedapro") (part "Device_R"))
    )
    (comp (ref "R61")
      (value "10kΩ")
      (footprint "easyedapro:Resistor_THT:R_Axial_DIN0204_L3.6mm_D1.6mm_P2.54mm_Vertical")
      (fields
        (field (name "Manufacturer Part") "RN 1/8W 4K7 F T/B A1")
        (field (name "Manufacturer") "Tyohm(幸亚电阻)")
      )
      (libsource (lib "easyedapro") (part "Device_R"))
    )
    (comp (ref "R62")
      (value "20kΩ")
      (footprint "easyedapro:Resistor_THT:R_Axial_DIN0204_L3.6mm_D1.6mm_P2.54mm_Vertical")
      (fields
        (field (name "Manufacturer Part") "RN 1/8W 4K7 F T/B A1")
        (field (name "Manufacturer") "Tyohm(幸亚电阻)")
      )
      (libsource (lib "easyedapro") (part "Device_R"))
    )
    (comp (ref "R63")
      (value "4.7kΩ")
      (footprint "easyedapro:Resistor_THT:R_Axial_DIN0204_L3.6mm_D1.6mm_P2.54mm_Vertical")
      (fields
        (field (name "Manufacturer Part") "RN 1/8W 4K7 F T/B A1")
        (field (name "Manufacturer") "Tyohm(幸亚电阻)")
      )
      (libsource (lib "easyedapro") (part "Device_R"))
    )
    (comp (ref "R64")
      (value "100kΩ")
      (footprint "easyedapro:Resistor_THT:R_Axial_DIN0204_L3.6mm_D1.6mm_P2.54mm_Vertical")
      (fields
        (field (name "Manufacturer Part") "RN 1/8W 4K7 F T/B A1")
        (field (name "Manufacturer") "Tyohm(幸亚电阻)")
      )
      (libsource (lib "easyedapro") (part "Device_R"))
    )
    (comp (ref "R65")
      (value "10kΩ")
      (footprint "easyedapro:Resistor_THT:R_Axial_DIN0204_L3.6mm_D1.6mm_P2.54mm_Vertical")
      (fields
        (field (name "Manufacturer Part") "RN 1/8W 4K7 F T/B A1")
        (field (name "Manufacturer") "Tyohm(幸亚电阻)")
      )
      (libsource (lib "easyedapro") (part "Device_R"))
    )
    (comp (ref "R66")
      (value "20kΩ")
      (footprint "easyedapro:Resistor_THT:R_Axial_DIN0204_L3.6mm_D1.6mm_P2.54mm_Vertical")
      (fields
        (field (name "Manufacturer Part") "RN 1/8W 4K7 F T/B A1")
        (field (name "Manufacturer") "Tyohm(幸亚电阻)")
      )
      (libsource (lib "easyedapro") (part "Device_R"))
    )
    (comp (ref "R67")
      (value "4.7kΩ")
      (footprint "easyedapro:Resistor_THT:R_Axial_DIN0204_L3.6mm_D1.6mm_P2.54mm_Vertical")
      (fields
        (field (name "Manufacturer Part") "RN 1/8W 4K7 F T/B A1")
        (field (name "Manufacturer") "Tyohm(幸亚电阻)")
      )
      (libsource (lib "easyedapro") (part "Device_R"))
    )
    (comp (ref "U21")
      (value "MCP6002DRG")
      (footprint "easyedapro:SOP-8_L4.9-W3.9-P1.27-LS6.0-BL")
      (fields (field (name "Manufacturer") "HGC(深圳汉芯)"))
      (libsource (lib "easyedapro") (part "MCP6002DRG"))
    )
    (comp (ref "U22")
      (value "MCP6002DRG")
      (footprint "easyedapro:SOP-8_L4.9-W3.9-P1.27-LS6.0-BL")
      (fields (field (name "Manufacturer") "HGC(深圳汉芯)"))
      (libsource (lib "easyedapro") (part "MCP6002DRG"))
    )
    (comp (ref "U23")
      (value "MCP6002DRG")
      (footprint "easyedapro:SOP-8_L4.9-W3.9-P1.27-LS6.0-BL")
      (fields (field (name "Manufacturer") "HGC(深圳汉芯)"))
      (libsource (lib "easyedapro") (part "MCP6002DRG"))
    )
    (comp (ref "C5")
      (value "220uF")
      (footprint "easyedapro:CAP-SMD_BD6.3-L6.6-W6.6-FD")
      (fields (field (name "Manufacturer Part") "189RV0019") (field (name "Manufacturer") "KNSCHA(科尼盛)"))
      (libsource (lib "easyedapro") (part "189RV0019"))
    )
    (comp (ref "C6")
      (value "100nF")
      (footprint "easyedapro:CAP-TH_L5.0-W2.5-P5.00-D1.0")
      (fields
        (field (name "Manufacturer Part") "CC1H104MC1FD3F6C10MF")
        (field (name "Manufacturer") "Dersonic(德尔创)")
      )
      (libsource (lib "easyedapro") (part "CC1H104MC1FD3F6C10MF"))
    )
    (comp (ref "C7")
      (value "100uF")
      (footprint "easyedapro:C1206")
      (description "Capacitance:100uF Tolerance:±20% Tolerance:±20% Voltage Rating:10V Temperature Coefficient:X5R")
      (fields
        (field (name "Manufacturer Part") "HGC1206R5107M100NSPJ")
        (field (name "Manufacturer") "Chinocera(华瓷)")
      )
      (libsource (lib "easyedapro") (part "HGC1206R5107M100NSPJ"))
    )
    (comp (ref "C8")
      (value "1uF")
      (footprint "easyedapro:Capacitor_THT:C_Disc_D3.4mm_W2.1mm_P2.50mm")
      (description "Capacitance:100nF Tolerance:±10% Tolerance:±10% Voltage Rating:63V Temperature Coefficient:-")
      (fields
        (field (name "Manufacturer Part") "CT4G-0805-2X1-63V-0.1μF-K")
        (field (name "Manufacturer") "TORCH(火炬)")
      )
      (libsource (lib "easyedapro") (part "Device_C"))
    )
    (comp (ref "C9")
      (value "100nF")
      (footprint "easyedapro:Capacitor_THT:C_Disc_D3.4mm_W2.1mm_P2.50mm")
      (description "Capacitance:100nF Tolerance:±10% Tolerance:±10% Voltage Rating:63V Temperature Coefficient:-")
      (fields
        (field (name "Manufacturer Part") "CT4G-0805-2X1-63V-0.1μF-K")
        (field (name "Manufacturer") "TORCH(火炬)")
      )
      (libsource (lib "easyedapro") (part "Device_C"))
    )
    (comp (ref "D44")
      (value "SA6.0A")
      (footprint "easyedapro:DO-15_BD3.1-L6.7-P10.70-D0.8-RD")
      (fields (field (name "Manufacturer") "Littelfuse(美国力特)"))
      (libsource (lib "easyedapro") (part "SA6.0A_C1973281"))
    )
    (comp (ref "F1")
      (value "nSMD050-33V")
      (footprint "easyedapro:F1206")
      (description "Voltage - Max:33V Current - Max:100A Hold Current:500mA Trip Current:1A")
      (fields (field (name "Manufacturer") "台湾陆海"))
      (libsource (lib "easyedapro") (part "nSMD050-33V"))
    )
    (comp (ref "J1")
      (value "DC005")
      (footprint "easyedapro:DC-IN-TH_DC005")
      (fields (field (name "Manufacturer") "SHOU HAN(首韩)"))
      (libsource (lib "easyedapro") (part "DC005_C431533"))
    )
    (comp (ref "R20")
      (value "33Ω")
      (footprint "easyedapro:Resistor_THT:R_Axial_DIN0204_L3.6mm_D1.6mm_P2.54mm_Vertical")
      (fields
        (field (name "Manufacturer Part") "RN1/8W10KFT/BA1")
        (field (name "Manufacturer") "Tyohm(幸亚电阻)")
      )
      (libsource (lib "easyedapro") (part "Device_R"))
    )
    (comp (ref "SW1")
      (value "HX B3F-4055-Y")
      (footprint "easyedapro:Button_Switch_SMD:SW_SPST_PTS645")
      (fields (field (name "Manufacturer") "hanxia(韩下)"))
      (libsource (lib "easyedapro") (part "Switch_SW_Push"))
    )
    (comp (ref "SW2")
      (value "HX B3F-4055-Y")
      (footprint "easyedapro:Button_Switch_SMD:SW_SPST_PTS645")
      (fields (field (name "Manufacturer") "hanxia(韩下)"))
      (libsource (lib "easyedapro") (part "Switch_SW_Push"))
    )
    (comp (ref "SW3")
      (value "HX B3F-4055-Y")
      (footprint "easyedapro:Button_Switch_SMD:SW_SPST_PTS645")
      (fields (field (name "Manufacturer") "hanxia(韩下)"))
      (libsource (lib "easyedapro") (part "Switch_SW_Push"))
    )
    (comp (ref "SW4")
      (value "HX B3F-4055-Y")
      (footprint "easyedapro:Button_Switch_SMD:SW_SPST_PTS645")
      (fields (field (name "Manufacturer") "hanxia(韩下)"))
      (libsource (lib "easyedapro") (part "Switch_SW_Push"))
    )
    (comp (ref "SW5")
      (value "HX B3F-4055-Y")
      (footprint "easyedapro:Button_Switch_SMD:SW_SPST_PTS645")
      (fields (field (name "Manufacturer") "hanxia(韩下)"))
      (libsource (lib "easyedapro") (part "Switch_SW_Push"))
    )
    (comp (ref "SW6")
      (value "HX B3F-4055-Y")
      (footprint "easyedapro:Button_Switch_SMD:SW_SPST_PTS645")
      (fields (field (name "Manufacturer") "hanxia(韩下)"))
      (libsource (lib "easyedapro") (part "Switch_SW_Push"))
    )
    (comp (ref "SW7")
      (value "HX B3F-4055-Y")
      (footprint "easyedapro:Button_Switch_SMD:SW_SPST_PTS645")
      (fields (field (name "Manufacturer") "hanxia(韩下)"))
      (libsource (lib "easyedapro") (part "Switch_SW_Push"))
    )
    (comp (ref "SW8")
      (value "HX B3F-4055-Y")
      (footprint "easyedapro:Button_Switch_SMD:SW_SPST_PTS645")
      (fields (field (name "Manufacturer") "hanxia(韩下)"))
      (libsource (lib "easyedapro") (part "Switch_SW_Push"))
    )
    (comp (ref "SW9")
      (value "HX B3F-4055-Y")
      (footprint "easyedapro:Button_Switch_SMD:SW_SPST_PTS645")
      (fields (field (name "Manufacturer") "hanxia(韩下)"))
      (libsource (lib "easyedapro") (part "Switch_SW_Push"))
    )
    (comp (ref "SW10")
      (value "HX B3F-4055-Y")
      (footprint "easyedapro:Button_Switch_SMD:SW_SPST_PTS645")
      (fields (field (name "Manufacturer") "hanxia(韩下)"))
      (libsource (lib "easyedapro") (part "Switch_SW_Push"))
    )
    (comp (ref "SW11")
      (value "HX B3F-4055-Y")
      (footprint "easyedapro:Button_Switch_SMD:SW_SPST_PTS645")
      (fields (field (name "Manufacturer") "hanxia(韩下)"))
      (libsource (lib "easyedapro") (part "Switch_SW_Push"))
    )
    (comp (ref "SW12")
      (value "HX B3F-4055-Y")
      (footprint "easyedapro:Button_Switch_SMD:SW_SPST_PTS645")
      (fields (field (name "Manufacturer") "hanxia(韩下)"))
      (libsource (lib "easyedapro") (part "Switch_SW_Push"))
    )
    (comp (ref "SW13")
      (value "HX B3F-4055-Y")
      (footprint "easyedapro:Button_Switch_SMD:SW_SPST_PTS645")
      (fields (field (name "Manufacturer") "hanxia(韩下)"))
      (libsource (lib "easyedapro") (part "Switch_SW_Push"))
    )
    (comp (ref "SW14")
      (value "HX B3F-4055-Y")
      (footprint "easyedapro:Button_Switch_SMD:SW_SPST_PTS645")
      (fields (field (name "Manufacturer") "hanxia(韩下)"))
      (libsource (lib "easyedapro") (part "Switch_SW_Push"))
    )
    (comp (ref "SW15")
      (value "HX B3F-4055-Y")
      (footprint "easyedapro:Button_Switch_SMD:SW_SPST_PTS645")
      (fields (field (name "Manufacturer") "hanxia(韩下)"))
      (libsource (lib "easyedapro") (part "Switch_SW_Push"))
    )
    (comp (ref "SW16")
      (value "HX B3F-4055-Y")
      (footprint "easyedapro:Button_Switch_SMD:SW_SPST_PTS645")
      (fields (field (name "Manufacturer") "hanxia(韩下)"))
      (libsource (lib "easyedapro") (part "Switch_SW_Push"))
    )
    (comp (ref "SW17")
      (value "HX B3F-4055-Y")
      (footprint "easyedapro:Button_Switch_SMD:SW_SPST_PTS645")
      (fields (field (name "Manufacturer") "hanxia(韩下)"))
      (libsource (lib "easyedapro") (part "Switch_SW_Push"))
    )
    (comp (ref "SW18")
      (value "HX B3F-4055-Y")
      (footprint "easyedapro:Button_Switch_SMD:SW_SPST_PTS645")
      (fields (field (name "Manufacturer") "hanxia(韩下)"))
      (libsource (lib "easyedapro") (part "Switch_SW_Push"))
    )
    (comp (ref "SW19")
      (value "HX B3F-4055-Y")
      (footprint "easyedapro:Button_Switch_SMD:SW_SPST_PTS645")
      (fields (field (name "Manufacturer") "hanxia(韩下)"))
      (libsource (lib "easyedapro") (part "Switch_SW_Push"))
    )
    (comp (ref "SW20")
      (value "HX B3F-4055-Y")
      (footprint "easyedapro:Button_Switch_SMD:SW_SPST_PTS645")
      (fields (field (name "Manufacturer") "hanxia(韩下)"))
      (libsource (lib "easyedapro") (part "Switch_SW_Push"))
    )
    (comp (ref "SW21")
      (value "HX B3F-4055-Y")
      (footprint "easyedapro:Button_Switch_SMD:SW_SPST_PTS645")
      (fields (field (name "Manufacturer") "hanxia(韩下)"))
      (libsource (lib "easyedapro") (part "Switch_SW_Push"))
    )
    (comp (ref "SW22")
      (value "HX B3F-4055-Y")
      (footprint "easyedapro:Button_Switch_SMD:SW_SPST_PTS645")
      (fields (field (name "Manufacturer") "hanxia(韩下)"))
      (libsource (lib "easyedapro") (part "Switch_SW_Push"))
    )
    (comp (ref "SW23")
      (value "HX B3F-4055-Y")
      (footprint "easyedapro:Button_Switch_SMD:SW_SPST_PTS645")
      (fields (field (name "Manufacturer") "hanxia(韩下)"))
      (libsource (lib "easyedapro") (part "Switch_SW_Push"))
    )
    (comp (ref "SW24")
      (value "HX B3F-4055-Y")
      (footprint "easyedapro:Button_Switch_SMD:SW_SPST_PTS645")
      (fields (field (name "Manufacturer") "hanxia(韩下)"))
      (libsource (lib "easyedapro") (part "Switch_SW_Push"))
    )
    (comp (ref "SW25")
      (value "HX B3F-4055-Y")
      (footprint "easyedapro:Button_Switch_SMD:SW_SPST_PTS645")
      (fields (field (name "Manufacturer") "hanxia(韩下)"))
      (libsource (lib "easyedapro") (part "Switch_SW_Push"))
    )
    (comp (ref "SW26")
      (value "HX B3F-4055-Y")
      (footprint "easyedapro:Button_Switch_SMD:SW_SPST_PTS645")
      (fields (field (name "Manufacturer") "hanxia(韩下)"))
      (libsource (lib "easyedapro") (part "Switch_SW_Push"))
    )
    (comp (ref "SW27")
      (value "HX B3F-4055-Y")
      (footprint "easyedapro:Button_Switch_SMD:SW_SPST_PTS645")
      (fields (field (name "Manufacturer") "hanxia(韩下)"))
      (libsource (lib "easyedapro") (part "Switch_SW_Push"))
    )
    (comp (ref "SW28")
      (value "HX B3F-4055-Y")
      (footprint "easyedapro:Button_Switch_SMD:SW_SPST_PTS645")
      (fields (field (name "Manufacturer") "hanxia(韩下)"))
      (libsource (lib "easyedapro") (part "Switch_SW_Push"))
    )
    (comp (ref "SW29")
      (value "HX B3F-4055-Y")
      (footprint "easyedapro:Button_Switch_SMD:SW_SPST_PTS645")
      (fields (field (name "Manufacturer") "hanxia(韩下)"))
      (libsource (lib "easyedapro") (part "Switch_SW_Push"))
    )
    (comp (ref "SW30")
      (value "HX B3F-4055-Y")
      (footprint "easyedapro:Button_Switch_SMD:SW_SPST_PTS645")
      (fields (field (name "Manufacturer") "hanxia(韩下)"))
      (libsource (lib "easyedapro") (part "Switch_SW_Push"))
    )
    (comp (ref "SW31")
      (value "HX B3F-4055-Y")
      (footprint "easyedapro:Button_Switch_SMD:SW_SPST_PTS645")
      (fields (field (name "Manufacturer") "hanxia(韩下)"))
      (libsource (lib "easyedapro") (part "Switch_SW_Push"))
    )
    (comp (ref "SW32")
      (value "HX B3F-4055-Y")
      (footprint "easyedapro:Button_Switch_SMD:SW_SPST_PTS645")
      (fields (field (name "Manufacturer") "hanxia(韩下)"))
      (libsource (lib "easyedapro") (part "Switch_SW_Push"))
    )
    (comp (ref "SW33")
      (value "HX B3F-4055-Y")
      (footprint "easyedapro:Button_Switch_SMD:SW_SPST_PTS645")
      (fields (field (name "Manufacturer") "hanxia(韩下)"))
      (libsource (lib "easyedapro") (part "Switch_SW_Push"))
    )
    (comp (ref "SW34")
      (value "HX B3F-4055-Y")
      (footprint "easyedapro:Button_Switch_SMD:SW_SPST_PTS645")
      (fields (field (name "Manufacturer") "hanxia(韩下)"))
      (libsource (lib "easyedapro") (part "Switch_SW_Push"))
    )
    (comp (ref "SW35")
      (value "HX B3F-4055-Y")
      (footprint "easyedapro:Button_Switch_SMD:SW_SPST_PTS645")
      (fields (field (name "Manufacturer") "hanxia(韩下)"))
      (libsource (lib "easyedapro") (part "Switch_SW_Push"))
    )
    (comp (ref "SW36")
      (value "HX B3F-4055-Y")
      (footprint "easyedapro:Button_Switch_SMD:SW_SPST_PTS645")
      (fields (field (name "Manufacturer") "hanxia(韩下)"))
      (libsource (lib "easyedapro") (part "Switch_SW_Push"))
    )
    (comp (ref "SW37")
      (value "HX B3F-4055-Y")
      (footprint "easyedapro:Button_Switch_SMD:SW_SPST_PTS645")
      (fields (field (name "Manufacturer") "hanxia(韩下)"))
      (libsource (lib "easyedapro") (part "Switch_SW_Push"))
    )
    (comp (ref "SW38")
      (value "HX B3F-4055-Y")
      (footprint "easyedapro:Button_Switch_SMD:SW_SPST_PTS645")
      (fields (field (name "Manufacturer") "hanxia(韩下)"))
      (libsource (lib "easyedapro") (part "Switch_SW_Push"))
    )
    (comp (ref "SW39")
      (value "HX B3F-4055-Y")
      (footprint "easyedapro:Button_Switch_SMD:SW_SPST_PTS645")
      (fields (field (name "Manufacturer") "hanxia(韩下)"))
      (libsource (lib "easyedapro") (part "Switch_SW_Push"))
    )
    (comp (ref "SW40")
      (value "HX B3F-4055-Y")
      (footprint "easyedapro:Button_Switch_SMD:SW_SPST_PTS645")
      (fields (field (name "Manufacturer") "hanxia(韩下)"))
      (libsource (lib "easyedapro") (part "Switch_SW_Push"))
    )
    (comp (ref "SW41")
      (value "HX B3F-4055-Y")
      (footprint "easyedapro:Button_Switch_SMD:SW_SPST_PTS645")
      (fields (field (name "Manufacturer") "hanxia(韩下)"))
      (libsource (lib "easyedapro") (part "Switch_SW_Push"))
    )
    (comp (ref "SW42")
      (value "HX B3F-4055-Y")
      (footprint "easyedapro:Button_Switch_SMD:SW_SPST_PTS645")
      (fields (field (name "Manufacturer") "hanxia(韩下)"))
      (libsource (lib "easyedapro") (part "Switch_SW_Push"))
    )
    (comp (ref "SW49")
      (value "TK-6580A-1")
      (footprint "easyedapro:SW-TH_TK-6580A-1")
      (fields (field (name "Manufacturer") "Yuandi(元迪)"))
      (libsource (lib "easyedapro") (part "TK-6580A-1"))
    )
    (comp (ref "U6")
      (value "1812L200/33GR")
      (footprint "easyedapro:F1812")
      (fields (field (name "Manufacturer") "LUTE(陆特)"))
      (libsource (lib "easyedapro") (part "1812L200/33GR"))
    )
    (comp (ref "U8")
      (value "SN74AHCT125N")
      (footprint "easyedapro:PDIP-14_L19.3-W6.4-P2.54-LS7.6-BL")
      (fields (field (name "Manufacturer") "TI(德州仪器)"))
      (libsource (lib "easyedapro") (part "SN74AHCT125N"))
    )
  )
  (nets
    (net (code "1") (name "3VDC") (class "Default")
      (node (ref "C25") (pin "2") (pinfunction "2_2") (pintype "unspecified"))
      (node (ref "C3") (pin "2") (pinfunction "~_2") (pintype "unspecified"))
      (node (ref "C4") (pin "2") (pinfunction "~_2") (pintype "unspecified"))
      (node (ref "C54") (pin "1") (pinfunction "~_1") (pintype "unspecified"))
      (node (ref "C56") (pin "1") (pinfunction "1_1") (pintype "input"))
      (node (ref "COL_MUX1") (pin "24") (pinfunction "VCC_24") (pintype "unspecified"))
      (node (ref "R2") (pin "1") (pinfunction "~_1") (pintype "unspecified"))
      (node (ref "R69") (pin "1") (pinfunction "~_1") (pintype "unspecified"))
      (node (ref "ROW_MUX1") (pin "24") (pinfunction "VCC_24") (pintype "unspecified"))
      (node (ref "RV1") (pin "1") (pinfunction "1_1") (pintype "unspecified"))
      (node (ref "RV2") (pin "1") (pinfunction "1_1") (pintype "unspecified"))
      (node (ref "RV3") (pin "1") (pinfunction "1_1") (pintype "unspecified"))
      (node (ref "SW43") (pin "2") (pinfunction "2_2") (pintype "unspecified"))
      (node (ref "SW44") (pin "2") (pinfunction "2_2") (pintype "unspecified"))
      (node (ref "SW45") (pin "2") (pinfunction "2_2") (pintype "unspecified"))
      (node (ref "SW46") (pin "2") (pinfunction "2_2") (pintype "unspecified"))
      (node (ref "SW47") (pin "2") (pinfunction "2_2") (pintype "unspecified"))
      (node (ref "SW48") (pin "2") (pinfunction "2_2") (pintype "unspecified"))
      (node (ref "Screen1") (pin "2") (pinfunction "Pin_2_2") (pintype "unspecified"))
      (node (ref "U1") (pin "3.3V_2") (pinfunction "3.3V_2_3.3V_2") (pintype "unspecified"))
      (node (ref "U21") (pin "8") (pinfunction "VDD_8") (pintype "unspecified"))
    )
    (net (code "2") (name "5VDC") (class "Default")
      (node (ref "C10") (pin "2") (pinfunction "~_2") (pintype "unspecified"))
      (node (ref "C8") (pin "1") (pinfunction "~_1") (pintype "unspecified"))
      (node (ref "C9") (pin "1") (pinfunction "~_1") (pintype "unspecified"))
      (node (ref "R4") (pin "2") (pinfunction "~_2") (pintype "unspecified"))
      (node (ref "R70") (pin "2") (pinfunction "~_2") (pintype "unspecified"))
      (node (ref "SW49") (pin "5") (pinfunction "5_5") (pintype "unspecified"))
      (node (ref "U5") (pin "7") (pinfunction "VO1_7") (pintype "unspecified"))
      (node (ref "U8") (pin "14") (pinfunction "VCC_14") (pintype "unspecified"))
    )
    (net (code "3") (name "CNTRLLP") (class "Default")
      (node (ref "C57") (pin "1") (pinfunction "~_1") (pintype "unspecified"))
      (node (ref "D42") (pin "3") (pinfunction "VSS_3") (pintype "unspecified"))
      (node (ref "D51") (pin "1") (pinfunction "VDD_1") (pintype "unspecified"))
    )
    (net (code "4") (name "CNTRL_LED") (class "Default")
      (node (ref "D42") (pin "2") (pinfunction "DOUT_2") (pintype "output"))
      (node (ref "D51") (pin "4") (pinfunction "DIN_4") (pintype "input"))
    )
    (net (code "5") (name "COL1") (class "Default")
      (node (ref "COL_MUX1") (pin "9") (pinfunction "I0_9") (pintype "unspecified"))
      (node (ref "SW1") (pin "2") (pinfunction "2_2") (pintype "unspecified"))
      (node (ref "SW2") (pin "2") (pinfunction "2_2") (pintype "unspecified"))
      (node (ref "SW3") (pin "2") (pinfunction "2_2") (pintype "unspecified"))
      (node (ref "SW4") (pin "2") (pinfunction "2_2") (pintype "unspecified"))
      (node (ref "SW5") (pin "2") (pinfunction "2_2") (pintype "unspecified"))
      (node (ref "SW6") (pin "2") (pinfunction "2_2") (pintype "unspecified"))
      (node (ref "SW7") (pin "2") (pinfunction "2_2") (pintype "unspecified"))
    )
    (net (code "6") (name "COL2") (class "Default")
      (node (ref "COL_MUX1") (pin "8") (pinfunction "I1_8") (pintype "unspecified"))
      (node (ref "SW10") (pin "2") (pinfunction "2_2") (pintype "unspecified"))
      (node (ref "SW11") (pin "2") (pinfunction "2_2") (pintype "unspecified"))
      (node (ref "SW12") (pin "2") (pinfunction "2_2") (pintype "unspecified"))
      (node (ref "SW13") (pin "2") (pinfunction "2_2") (pintype "unspecified"))
      (node (ref "SW14") (pin "2") (pinfunction "2_2") (pintype "unspecified"))
      (node (ref "SW8") (pin "2") (pinfunction "2_2") (pintype "unspecified"))
      (node (ref "SW9") (pin "2") (pinfunction "2_2") (pintype "unspecified"))
    )
    (net (code "7") (name "COL3") (class "Default")
      (node (ref "COL_MUX1") (pin "7") (pinfunction "I2_7") (pintype "unspecified"))
      (node (ref "SW15") (pin "2") (pinfunction "2_2") (pintype "unspecified"))
      (node (ref "SW16") (pin "2") (pinfunction "2_2") (pintype "unspecified"))
      (node (ref "SW17") (pin "2") (pinfunction "2_2") (pintype "unspecified"))
      (node (ref "SW18") (pin "2") (pinfunction "2_2") (pintype "unspecified"))
      (node (ref "SW19") (pin "2") (pinfunction "2_2") (pintype "unspecified"))
      (node (ref "SW20") (pin "2") (pinfunction "2_2") (pintype "unspecified"))
      (node (ref "SW21") (pin "2") (pinfunction "2_2") (pintype "unspecified"))
    )
    (net (code "8") (name "COL4") (class "Default")
      (node (ref "COL_MUX1") (pin "6") (pinfunction "I3_6") (pintype "unspecified"))
      (node (ref "SW22") (pin "2") (pinfunction "2_2") (pintype "unspecified"))
      (node (ref "SW23") (pin "2") (pinfunction "2_2") (pintype "unspecified"))
      (node (ref "SW24") (pin "2") (pinfunction "2_2") (pintype "unspecified"))
      (node (ref "SW25") (pin "2") (pinfunction "2_2") (pintype "unspecified"))
      (node (ref "SW26") (pin "2") (pinfunction "2_2") (pintype "unspecified"))
      (node (ref "SW27") (pin "2") (pinfunction "2_2") (pintype "unspecified"))
      (node (ref "SW28") (pin "2") (pinfunction "2_2") (pintype "unspecified"))
    )
    (net (code "9") (name "COL5") (class "Default")
      (node (ref "COL_MUX1") (pin "5") (pinfunction "I4_5") (pintype "unspecified"))
      (node (ref "SW29") (pin "2") (pinfunction "2_2") (pintype "unspecified"))
      (node (ref "SW30") (pin "2") (pinfunction "2_2") (pintype "unspecified"))
      (node (ref "SW31") (pin "2") (pinfunction "2_2") (pintype "unspecified"))
      (node (ref "SW32") (pin "2") (pinfunction "2_2") (pintype "unspecified"))
      (node (ref "SW33") (pin "2") (pinfunction "2_2") (pintype "unspecified"))
      (node (ref "SW34") (pin "2") (pinfunction "2_2") (pintype "unspecified"))
      (node (ref "SW35") (pin "2") (pinfunction "2_2") (pintype "unspecified"))
    )
    (net (code "10") (name "COL6") (class "Default")
      (node (ref "COL_MUX1") (pin "4") (pinfunction "I5_4") (pintype "unspecified"))
      (node (ref "SW36") (pin "2") (pinfunction "2_2") (pintype "unspecified"))
      (node (ref "SW37") (pin "2") (pinfunction "2_2") (pintype "unspecified"))
      (node (ref "SW38") (pin "2") (pinfunction "2_2") (pintype "unspecified"))
      (node (ref "SW39") (pin "2") (pinfunction "2_2") (pintype "unspecified"))
      (node (ref "SW40") (pin "2") (pinfunction "2_2") (pintype "unspecified"))
      (node (ref "SW41") (pin "2") (pinfunction "2_2") (pintype "unspecified"))
      (node (ref "SW42") (pin "2") (pinfunction "2_2") (pintype "unspecified"))
    )
    (net (code "11") (name "CTRL1") (class "Default")
      (node (ref "COL_MUX1") (pin "2") (pinfunction "I7_2") (pintype "unspecified"))
      (node (ref "SW43") (pin "1") (pinfunction "1_1") (pintype "unspecified"))
    )
    (net (code "12") (name "CTRL2") (class "Default")
      (node (ref "COL_MUX1") (pin "23") (pinfunction "I8_23") (pintype "unspecified"))
      (node (ref "SW44") (pin "1") (pinfunction "1_1") (pintype "unspecified"))
    )
    (net (code "13") (name "CTRL3") (class "Default")
      (node (ref "COL_MUX1") (pin "22") (pinfunction "I9_22") (pintype "unspecified"))
      (node (ref "SW45") (pin "1") (pinfunction "1_1") (pintype "unspecified"))
    )
    (net (code "14") (name "CTRL4") (class "Default")
      (node (ref "COL_MUX1") (pin "21") (pinfunction "I10_21") (pintype "unspecified"))
      (node (ref "SW46") (pin "1") (pinfunction "1_1") (pintype "unspecified"))
    )
    (net (code "15") (name "CTRL5") (class "Default")
      (node (ref "COL_MUX1") (pin "20") (pinfunction "I11_20") (pintype "unspecified"))
      (node (ref "SW47") (pin "1") (pinfunction "1_1") (pintype "unspecified"))
    )
    (net (code "16") (name "CTRL6") (class "Default")
      (node (ref "COL_MUX1") (pin "19") (pinfunction "I12_19") (pintype "unspecified"))
      (node (ref "SW48") (pin "1") (pinfunction "1_1") (pintype "unspecified"))
    )
    (net (code "17") (name "E1") (class "Default")
      (node (ref "C12") (pin "1") (pinfunction "1_1") (pintype "input"))
      (node (ref "R25") (pin "2") (pinfunction "~_2") (pintype "unspecified"))
      (node (ref "U1") (pin "14") (pinfunction "14_14") (pintype "bidirectional"))
    )
    (net (code "18") (name "E2") (class "Default")
      (node (ref "C43") (pin "1") (pinfunction "1_1") (pintype "input"))
      (node (ref "R55") (pin "2") (pinfunction "~_2") (pintype "unspecified"))
      (node (ref "U1") (pin "15") (pinfunction "15_15") (pintype "bidirectional"))
    )
    (net (code "19") (name "E3") (class "Default")
      (node (ref "C46") (pin "1") (pinfunction "1_1") (pintype "input"))
      (node (ref "R59") (pin "2") (pinfunction "~_2") (pintype "unspecified"))
      (node (ref "U1") (pin "16") (pinfunction "16_16") (pintype "bidirectional"))
    )
    (net (code "20") (name "E4") (class "Default")
      (node (ref "C40") (pin "1") (pinfunction "1_1") (pintype "input"))
      (node (ref "R51") (pin "2") (pinfunction "~_2") (pintype "unspecified"))
      (node (ref "U1") (pin "17") (pinfunction "17_17") (pintype "bidirectional"))
    )
    (net (code "21") (name "E5") (class "Default")
      (node (ref "C49") (pin "1") (pinfunction "1_1") (pintype "input"))
      (node (ref "R63") (pin "2") (pinfunction "~_2") (pintype "unspecified"))
      (node (ref "U1") (pin "20") (pinfunction "20_20") (pintype "bidirectional"))
    )
    (net (code "22") (name "E6") (class "Default")
      (node (ref "C52") (pin "1") (pinfunction "1_1") (pintype "input"))
      (node (ref "R67") (pin "2") (pinfunction "~_2") (pintype "unspecified"))
      (node (ref "U1") (pin "21") (pinfunction "21_21") (pintype "bidirectional"))
    )
    (net (code "23") (name "FP1") (class "Default")
      (node (ref "COL_MUX1") (pin "17") (pinfunction "I14_17") (pintype "unspecified"))
      (node (ref "RV1") (pin "2") (pinfunction "2_2") (pintype "unspecified"))
    )
    (net (code "24") (name "FP2") (class "Default")
      (node (ref "COL_MUX1") (pin "16") (pinfunction "I15_16") (pintype "unspecified"))
      (node (ref "RV2") (pin "2") (pinfunction "2_2") (pintype "unspecified"))
    )
    (net (code "25") (name "GND") (class "Default")
      (node (ref "C10") (pin "1") (pinfunction "~_1") (pintype "unspecified"))
      (node (ref "C12") (pin "2") (pinfunction "2_2") (pintype "input"))
      (node (ref "C2") (pin "2") (pinfunction "~_2") (pintype "unspecified"))
      (node (ref "C3") (pin "1") (pinfunction "~_1") (pintype "unspecified"))
      (node (ref "C31") (pin "2") (pinfunction "~_2") (pintype "unspecified"))
      (node (ref "C32") (pin "2") (pinfunction "~_2") (pintype "unspecified"))
      (node (ref "C33") (pin "2") (pinfunction "~_2") (pintype "unspecified"))
      (node (ref "C34") (pin "2") (pinfunction "~_2") (pintype "unspecified"))
      (node (ref "C35") (pin "2") (pinfunction "~_2") (pintype "unspecified"))
      (node (ref "C36") (pin "2") (pinfunction "~_2") (pintype "unspecified"))
      (node (ref "C4") (pin "1") (pinfunction "~_1") (pintype "unspecified"))
      (node (ref "C40") (pin "2") (pinfunction "2_2") (pintype "input"))
      (node (ref "C43") (pin "2") (pinfunction "2_2") (pintype "input"))
      (node (ref "C46") (pin "2") (pinfunction "2_2") (pintype "input"))
      (node (ref "C49") (pin "2") (pinfunction "2_2") (pintype "input"))
      (node (ref "C5") (pin "1") (pinfunction "1_1") (pintype "input"))
      (node (ref "C52") (pin "2") (pinfunction "2_2") (pintype "input"))
      (node (ref "C54") (pin "2") (pinfunction "~_2") (pintype "unspecified"))
      (node (ref "C56") (pin "2") (pinfunction "2_2") (pintype "input"))
      (node (ref "C57") (pin "2") (pinfunction "~_2") (pintype "unspecified"))
      (node (ref "C59") (pin "2") (pinfunction "~_2") (pintype "unspecified"))
      (node (ref "C6") (pin "1") (pinfunction "1_1") (pintype "unspecified"))
      (node (ref "C7") (pin "1") (pinfunction "1_1") (pintype "unspecified"))
      (node (ref "C8") (pin "2") (pinfunction "~_2") (pintype "unspecified"))
      (node (ref "C9") (pin "2") (pinfunction "~_2") (pintype "unspecified"))
      (node (ref "COL_MUX1") (pin "12") (pinfunction "GND_12") (pintype "unspecified"))
      (node (ref "COL_MUX1") (pin "15") (pinfunction "~{E}_15") (pintype "input"))
      (node (ref "COL_MUX1") (pin "3") (pinfunction "I6_3") (pintype "unspecified"))
      (node (ref "D44") (pin "2") (pinfunction "A_2") (pintype "input"))
      (node (ref "D56") (pin "3") (pinfunction "VSS_3") (pintype "unspecified"))
      (node (ref "D58") (pin "2") (pinfunction "DOUT_2") (pintype "output"))
      (node (ref "D58") (pin "3") (pinfunction "VSS_3") (pintype "unspecified"))
      (node (ref "J1") (pin "2") (pinfunction "2_2") (pintype "unspecified"))
      (node (ref "J1") (pin "3") (pinfunction "3_3") (pintype "unspecified"))
      (node (ref "J10") (pin "1") (pinfunction "1_1") (pintype "unspecified"))
      (node (ref "J10") (pin "3") (pinfunction "3_3") (pintype "unspecified"))
      (node (ref "J11") (pin "1") (pinfunction "1_1") (pintype "unspecified"))
      (node (ref "J11") (pin "3") (pinfunction "3_3") (pintype "unspecified"))
      (node (ref "J2") (pin "2") (pinfunction "2_2") (pintype "unspecified"))
      (node (ref "J3") (pin "2") (pinfunction "2_2") (pintype "unspecified"))
      (node (ref "J4") (pin "1") (pinfunction "1_1") (pintype "unspecified"))
      (node (ref "J4") (pin "2") (pinfunction "2_2") (pintype "unspecified"))
      (node (ref "J4") (pin "3") (pinfunction "3_3") (pintype "unspecified"))
      (node (ref "J5") (pin "1") (pinfunction "1_1") (pintype "unspecified"))
      (node (ref "J5") (pin "2") (pinfunction "2_2") (pintype "unspecified"))
      (node (ref "J5") (pin "3") (pinfunction "3_3") (pintype "unspecified"))
      (node (ref "J6") (pin "1") (pinfunction "1_1") (pintype "unspecified"))
      (node (ref "J6") (pin "2") (pinfunction "2_2") (pintype "unspecified"))
      (node (ref "J6") (pin "3") (pinfunction "3_3") (pintype "unspecified"))
      (node (ref "J7") (pin "1") (pinfunction "1_1") (pintype "unspecified"))
      (node (ref "J7") (pin "2") (pinfunction "2_2") (pintype "unspecified"))
      (node (ref "J7") (pin "3") (pinfunction "3_3") (pintype "unspecified"))
      (node (ref "J8") (pin "1") (pinfunction "1_1") (pintype "unspecified"))
      (node (ref "J8") (pin "2") (pinfunction "2_2") (pintype "unspecified"))
      (node (ref "J8") (pin "3") (pinfunction "3_3") (pintype "unspecified"))
      (node (ref "J9") (pin "1") (pinfunction "1_1") (pintype "unspecified"))
      (node (ref "J9") (pin "2") (pinfunction "2_2") (pintype "unspecified"))
      (node (ref "J9") (pin "3") (pinfunction "3_3") (pintype "unspecified"))
      (node (ref "LEDPWR1") (pin "1") (pinfunction "C_1") (pintype "input"))
      (node (ref "R22") (pin "1") (pinfunction "~_1") (pintype "unspecified"))
      (node (ref "R24") (pin "2") (pinfunction "~_2") (pintype "unspecified"))
      (node (ref "R48") (pin "1") (pinfunction "~_1") (pintype "unspecified"))
      (node (ref "R50") (pin "2") (pinfunction "~_2") (pintype "unspecified"))
      (node (ref "R52") (pin "1") (pinfunction "~_1") (pintype "unspecified"))
      (node (ref "R54") (pin "2") (pinfunction "~_2") (pintype "unspecified"))
      (node (ref "R56") (pin "1") (pinfunction "~_1") (pintype "unspecified"))
      (node (ref "R58") (pin "2") (pinfunction "~_2") (pintype "unspecified"))
      (node (ref "R60") (pin "1") (pinfunction "~_1") (pintype "unspecified"))
      (node (ref "R62") (pin "2") (pinfunction "~_2") (pintype "unspecified"))
      (node (ref "R64") (pin "1") (pinfunction "~_1") (pintype "unspecified"))
      (node (ref "R66") (pin "2") (pinfunction "~_2") (pintype "unspecified"))
      (node (ref "ROW_MUX1") (pin "12") (pinfunction "GND_12") (pintype "unspecified"))
      (node (ref "ROW_MUX1") (pin "15") (pinfunction "~{E}_15") (pintype "input"))
      (node (ref "ROW_MUX1") (pin "16") (pinfunction "I15_16") (pintype "unspecified"))
      (node (ref "ROW_MUX1") (pin "17") (pinfunction "I14_17") (pintype "unspecified"))
      (node (ref "ROW_MUX1") (pin "18") (pinfunction "I13_18") (pintype "unspecified"))
      (node (ref "ROW_MUX1") (pin "19") (pinfunction "I12_19") (pintype "unspecified"))
      (node (ref "ROW_MUX1") (pin "20") (pinfunction "I11_20") (pintype "unspecified"))
      (node (ref "ROW_MUX1") (pin "21") (pinfunction "I10_21") (pintype "unspecified"))
      (node (ref "ROW_MUX1") (pin "22") (pinfunction "I9_22") (pintype "unspecified"))
      (node (ref "ROW_MUX1") (pin "23") (pinfunction "I8_23") (pintype "unspecified"))
      (node (ref "RV1") (pin "3") (pinfunction "3_3") (pintype "unspecified"))
      (node (ref "RV1") (pin "4") (pinfunction "EH_4") (pintype "unspecified"))
      (node (ref "RV1") (pin "5") (pinfunction "EH_5") (pintype "unspecified"))
      (node (ref "RV2") (pin "3") (pinfunction "3_3") (pintype "unspecified"))
      (node (ref "RV2") (pin "4") (pinfunction "EH_4") (pintype "unspecified"))
      (node (ref "RV2") (pin "5") (pinfunction "EH_5") (pintype "unspecified"))
      (node (ref "RV3") (pin "3") (pinfunction "3_3") (pintype "unspecified"))
      (node (ref "RV3") (pin "4") (pinfunction "EH_4") (pintype "unspecified"))
      (node (ref "RV3") (pin "5") (pinfunction "EH_5") (pintype "unspecified"))
      (node (ref "SW49") (pin "1") (pinfunction "1_1") (pintype "unspecified"))
      (node (ref "SW49") (pin "3") (pinfunction "3_3") (pintype "unspecified"))
      (node (ref "Screen1") (pin "1") (pinfunction "Pin_1_1") (pintype "unspecified"))
      (node (ref "U1") (pin "G1") (pinfunction "G1_G1") (pintype "unspecified"))
      (node (ref "U1") (pin "G3") (pinfunction "G3_G3") (pintype "unspecified"))
      (node (ref "U5") (pin "5") (pinfunction "GND_5") (pintype "unspecified"))
      (node (ref "U5") (pin "8") (pinfunction "VCC_8") (pintype "unspecified"))
      (node (ref "U8") (pin "1") (pinfunction "#1OE_1") (pintype "unspecified"))
      (node (ref "U8") (pin "10") (pinfunction "#3OE_10") (pintype "unspecified"))
      (node (ref "U8") (pin "11") (pinfunction "4Y_11") (pintype "unspecified"))
      (node (ref "U8") (pin "12") (pinfunction "4A_12") (pintype "unspecified"))
      (node (ref "U8") (pin "13") (pinfunction "#4OE_13") (pintype "unspecified"))
      (node (ref "U8") (pin "4") (pinfunction "#2OE_4") (pintype "unspecified"))
      (node (ref "U8") (pin "7") (pinfunction "GND_7") (pintype "unspecified"))
      (node (ref "U8") (pin "8") (pinfunction "3Y_8") (pintype "unspecified"))
      (node (ref "U8") (pin "9") (pinfunction "3A_9") (pintype "unspecified"))
    )
    (net (code "26") (name "LED") (class "Default")
      (node (ref "U1") (pin "6") (pinfunction "6_6") (pintype "bidirectional"))
      (node (ref "U8") (pin "2") (pinfunction "1A_2") (pintype "unspecified"))
    )
    (net (code "27") (name "LEDCNTRL") (class "Default")
      (node (ref "D1") (pin "4") (pinfunction "DIN_4") (pintype "input"))
      (node (ref "R20") (pin "2") (pinfunction "~_2") (pintype "unspecified"))
    )
    (net (code "28") (name "MAIN") (class "Default")
      (node (ref "COL_MUX1") (pin "18") (pinfunction "I13_18") (pintype "unspecified"))
      (node (ref "RV3") (pin "2") (pinfunction "2_2") (pintype "unspecified"))
    )
    (net (code "29") (name "MIDI_OUT") (class "Default")
      (node (ref "R19") (pin "2") (pinfunction "~_2") (pintype "unspecified"))
      (node (ref "R71") (pin "2") (pinfunction "~_2") (pintype "unspecified"))
      (node (ref "U8") (pin "6") (pinfunction "2Y_6") (pintype "unspecified"))
    )
    (net (code "30") (name "MIDI_RX") (class "Default")
      (node (ref "R2") (pin "2") (pinfunction "~_2") (pintype "unspecified"))
      (node (ref "U1") (pin "0") (pinfunction "0_0") (pintype "bidirectional"))
      (node (ref "U5") (pin "6") (pinfunction "VO2_6") (pintype "unspecified"))
    )
    (net (code "31") (name "MIDI_TX") (class "Default")
      (node (ref "U1") (pin "1") (pinfunction "1_1") (pintype "bidirectional"))
      (node (ref "U8") (pin "5") (pinfunction "2A_5") (pintype "unspecified"))
    )
    (net (code "32") (name "MRC") (class "Default")
      (node (ref "COL_MUX1") (pin "1") (pinfunction "COM_1") (pintype "unspecified"))
      (node (ref "U1") (pin "7") (pinfunction "7_7") (pintype "bidirectional"))
    )
    (net (code "33") (name "MRR") (class "Default")
      (node (ref "ROW_MUX1") (pin "1") (pinfunction "COM_1") (pintype "unspecified"))
      (node (ref "U1") (pin "22") (pinfunction "22_22") (pintype "bidirectional"))
    )
    (net (code "34") (name "MUXC1") (class "Default")
      (node (ref "COL_MUX1") (pin "10") (pinfunction "S0_10") (pintype "input"))
      (node (ref "U1") (pin "8") (pinfunction "8_8") (pintype "bidirectional"))
    )
    (net (code "35") (name "MUXC2") (class "Default")
      (node (ref "COL_MUX1") (pin "11") (pinfunction "S1_11") (pintype "input"))
      (node (ref "U1") (pin "9") (pinfunction "9_9") (pintype "bidirectional"))
    )
    (net (code "36") (name "MUXC3") (class "Default")
      (node (ref "COL_MUX1") (pin "14") (pinfunction "S2_14") (pintype "input"))
      (node (ref "U1") (pin "10") (pinfunction "10_10") (pintype "bidirectional"))
    )
    (net (code "37") (name "MUXC4") (class "Default")
      (node (ref "COL_MUX1") (pin "13") (pinfunction "S3_13") (pintype "input"))
      (node (ref "U1") (pin "11") (pinfunction "11_11") (pintype "bidirectional"))
    )
    (net (code "38") (name "MUXR1") (class "Default")
      (node (ref "ROW_MUX1") (pin "10") (pinfunction "S0_10") (pintype "input"))
      (node (ref "U1") (pin "2") (pinfunction "2_2") (pintype "bidirectional"))
    )
    (net (code "39") (name "MUXR2") (class "Default")
      (node (ref "ROW_MUX1") (pin "11") (pinfunction "S1_11") (pintype "input"))
      (node (ref "U1") (pin "3") (pinfunction "3_3") (pintype "bidirectional"))
    )
    (net (code "40") (name "MUXR3") (class "Default")
      (node (ref "ROW_MUX1") (pin "14") (pinfunction "S2_14") (pintype "input"))
      (node (ref "U1") (pin "4") (pinfunction "4_4") (pintype "bidirectional"))
    )
    (net (code "41") (name "MUXR4") (class "Default")
      (node (ref "ROW_MUX1") (pin "13") (pinfunction "S3_13") (pintype "input"))
      (node (ref "U1") (pin "5") (pinfunction "5_5") (pintype "bidirectional"))
    )
    (net (code "42") (name "Net-(C11-Pad1)") (class "Default")
      (node (ref "C11") (pin "1") (pinfunction "1_1") (pintype "input"))
      (node (ref "J4") (pin "4") (pinfunction "4_4") (pintype "unspecified"))
    )
    (net (code "43") (name "Net-(C11-Pad2)") (class "Default")
      (node (ref "C11") (pin "2") (pinfunction "2_2") (pintype "input"))
      (node (ref "R22") (pin "2") (pinfunction "~_2") (pintype "unspecified"))
      (node (ref "R23") (pin "2") (pinfunction "~_2") (pintype "unspecified"))
    )
    (net (code "44") (name "Net-(C37-~-Pad1)") (class "Default")
      (node (ref "C37") (pin "1") (pinfunction "~_1") (pintype "unspecified"))
      (node (ref "C38") (pin "1") (pinfunction "1_1") (pintype "input"))
      (node (ref "R46") (pin "1") (pinfunction "~_1") (pintype "unspecified"))
      (node (ref "U1") (pin "G2") (pinfunction "G2_G2") (pintype "unspecified"))
    )
    (net (code "45") (name "Net-(C37-~-Pad2)") (class "Default")
      (node (ref "C37") (pin "2") (pinfunction "~_2") (pintype "unspecified"))
      (node (ref "C38") (pin "2") (pinfunction "2_2") (pintype "input"))
      (node (ref "R47") (pin "1") (pinfunction "~_1") (pintype "unspecified"))
      (node (ref "U1") (pin "3.3V_1") (pinfunction "3.3V_1_3.3V_1") (pintype "unspecified"))
    )
    (net (code "46") (name "Net-(C39-Pad1)") (class "Default")
      (node (ref "C39") (pin "1") (pinfunction "1_1") (pintype "input"))
      (node (ref "J5") (pin "4") (pinfunction "4_4") (pintype "unspecified"))
    )
    (net (code "47") (name "Net-(C39-Pad2)") (class "Default")
      (node (ref "C39") (pin "2") (pinfunction "2_2") (pintype "input"))
      (node (ref "R48") (pin "2") (pinfunction "~_2") (pintype "unspecified"))
      (node (ref "R49") (pin "2") (pinfunction "~_2") (pintype "unspecified"))
    )
    (net (code "48") (name "Net-(C42-Pad1)") (class "Default")
      (node (ref "C42") (pin "1") (pinfunction "1_1") (pintype "input"))
      (node (ref "J6") (pin "4") (pinfunction "4_4") (pintype "unspecified"))
    )
    (net (code "49") (name "Net-(C42-Pad2)") (class "Default")
      (node (ref "C42") (pin "2") (pinfunction "2_2") (pintype "input"))
      (node (ref "R52") (pin "2") (pinfunction "~_2") (pintype "unspecified"))
      (node (ref "R53") (pin "2") (pinfunction "~_2") (pintype "unspecified"))
    )
    (net (code "50") (name "Net-(C45-Pad1)") (class "Default")
      (node (ref "C45") (pin "1") (pinfunction "1_1") (pintype "input"))
      (node (ref "J7") (pin "4") (pinfunction "4_4") (pintype "unspecified"))
    )
    (net (code "51") (name "Net-(C45-Pad2)") (class "Default")
      (node (ref "C45") (pin "2") (pinfunction "2_2") (pintype "input"))
      (node (ref "R56") (pin "2") (pinfunction "~_2") (pintype "unspecified"))
      (node (ref "R57") (pin "2") (pinfunction "~_2") (pintype "unspecified"))
    )
    (net (code "52") (name "Net-(C48-Pad1)") (class "Default")
      (node (ref "C48") (pin "1") (pinfunction "1_1") (pintype "input"))
      (node (ref "J8") (pin "4") (pinfunction "4_4") (pintype "unspecified"))
    )
    (net (code "53") (name "Net-(C48-Pad2)") (class "Default")
      (node (ref "C48") (pin "2") (pinfunction "2_2") (pintype "input"))
      (node (ref "R60") (pin "2") (pinfunction "~_2") (pintype "unspecified"))
      (node (ref "R61") (pin "2") (pinfunction "~_2") (pintype "unspecified"))
    )
    (net (code "54") (name "Net-(C51-Pad1)") (class "Default")
      (node (ref "C51") (pin "1") (pinfunction "1_1") (pintype "input"))
      (node (ref "J9") (pin "4") (pinfunction "4_4") (pintype "unspecified"))
    )
    (net (code "55") (name "Net-(C51-Pad2)") (class "Default")
      (node (ref "C51") (pin "2") (pinfunction "2_2") (pintype "input"))
      (node (ref "R64") (pin "2") (pinfunction "~_2") (pintype "unspecified"))
      (node (ref "R65") (pin "2") (pinfunction "~_2") (pintype "unspecified"))
    )
    (net (code "56") (name "Net-(D1-DOUT)") (class "Default")
      (node (ref "D1") (pin "2") (pinfunction "DOUT_2") (pintype "output"))
      (node (ref "D2") (pin "4") (pinfunction "DIN_4") (pintype "input"))
    )
    (net (code "57") (name "Net-(D1-VSS)") (class "Default")
      (node (ref "D1") (pin "3") (pinfunction "VSS_3") (pintype "unspecified"))
      (node (ref "D2") (pin "1") (pinfunction "VDD_1") (pintype "unspecified"))
    )
    (net (code "58") (name "Net-(D2-DOUT)") (class "Default")
      (node (ref "D2") (pin "2") (pinfunction "DOUT_2") (pintype "output"))
      (node (ref "D3") (pin "4") (pinfunction "DIN_4") (pintype "input"))
    )
    (net (code "59") (name "Net-(D2-VSS)") (class "Default")
      (node (ref "D2") (pin "3") (pinfunction "VSS_3") (pintype "unspecified"))
      (node (ref "D3") (pin "1") (pinfunction "VDD_1") (pintype "unspecified"))
    )
    (net (code "60") (name "Net-(D3-DOUT)") (class "Default")
      (node (ref "D3") (pin "2") (pinfunction "DOUT_2") (pintype "output"))
      (node (ref "D4") (pin "4") (pinfunction "DIN_4") (pintype "input"))
    )
    (net (code "61") (name "Net-(D3-VSS)") (class "Default")
      (node (ref "D3") (pin "3") (pinfunction "VSS_3") (pintype "unspecified"))
      (node (ref "D4") (pin "1") (pinfunction "VDD_1") (pintype "unspecified"))
    )
    (net (code "62") (name "Net-(D4-DOUT)") (class "Default")
      (node (ref "D4") (pin "2") (pinfunction "DOUT_2") (pintype "output"))
      (node (ref "D5") (pin "4") (pinfunction "DIN_4") (pintype "input"))
    )
    (net (code "63") (name "Net-(D4-VSS)") (class "Default")
      (node (ref "D4") (pin "3") (pinfunction "VSS_3") (pintype "unspecified"))
      (node (ref "D5") (pin "1") (pinfunction "VDD_1") (pintype "unspecified"))
    )
    (net (code "64") (name "Net-(D5-DOUT)") (class "Default")
      (node (ref "D5") (pin "2") (pinfunction "DOUT_2") (pintype "output"))
      (node (ref "D6") (pin "4") (pinfunction "DIN_4") (pintype "input"))
    )
    (net (code "65") (name "Net-(D5-VSS)") (class "Default")
      (node (ref "D5") (pin "3") (pinfunction "VSS_3") (pintype "unspecified"))
      (node (ref "D6") (pin "1") (pinfunction "VDD_1") (pintype "unspecified"))
    )
    (net (code "66") (name "Net-(D6-DOUT)") (class "Default")
      (node (ref "D6") (pin "2") (pinfunction "DOUT_2") (pintype "output"))
      (node (ref "D7") (pin "4") (pinfunction "DIN_4") (pintype "input"))
    )
    (net (code "67") (name "Net-(D6-VSS)") (class "Default")
      (node (ref "C31") (pin "1") (pinfunction "~_1") (pintype "unspecified"))
      (node (ref "D6") (pin "3") (pinfunction "VSS_3") (pintype "unspecified"))
      (node (ref "D7") (pin "1") (pinfunction "VDD_1") (pintype "unspecified"))
    )
    (net (code "68") (name "Net-(D7-DOUT)") (class "Default")
      (node (ref "D7") (pin "2") (pinfunction "DOUT_2") (pintype "output"))
      (node (ref "D8") (pin "4") (pinfunction "DIN_4") (pintype "input"))
    )
    (net (code "69") (name "Net-(D7-VSS)") (class "Default")
      (node (ref "D7") (pin "3") (pinfunction "VSS_3") (pintype "unspecified"))
      (node (ref "D8") (pin "1") (pinfunction "VDD_1") (pintype "unspecified"))
    )
    (net (code "70") (name "Net-(D8-DOUT)") (class "Default")
      (node (ref "D8") (pin "2") (pinfunction "DOUT_2") (pintype "output"))
      (node (ref "D9") (pin "4") (pinfunction "DIN_4") (pintype "input"))
    )
    (net (code "71") (name "Net-(D8-VSS)") (class "Default")
      (node (ref "D8") (pin "3") (pinfunction "VSS_3") (pintype "unspecified"))
      (node (ref "D9") (pin "1") (pinfunction "VDD_1") (pintype "unspecified"))
    )
    (net (code "72") (name "Net-(D10-DIN)") (class "Default")
      (node (ref "D10") (pin "4") (pinfunction "DIN_4") (pintype "input"))
      (node (ref "D9") (pin "2") (pinfunction "DOUT_2") (pintype "output"))
    )
    (net (code "73") (name "Net-(D10-DOUT)") (class "Default")
      (node (ref "D10") (pin "2") (pinfunction "DOUT_2") (pintype "output"))
      (node (ref "D11") (pin "4") (pinfunction "DIN_4") (pintype "input"))
    )
    (net (code "74") (name "Net-(D10-VDD)") (class "Default")
      (node (ref "D10") (pin "1") (pinfunction "VDD_1") (pintype "unspecified"))
      (node (ref "D9") (pin "3") (pinfunction "VSS_3") (pintype "unspecified"))
    )
    (net (code "75") (name "Net-(D10-VSS)") (class "Default")
      (node (ref "D10") (pin "3") (pinfunction "VSS_3") (pintype "unspecified"))
      (node (ref "D11") (pin "1") (pinfunction "VDD_1") (pintype "unspecified"))
    )
    (net (code "76") (name "Net-(D11-DOUT)") (class "Default")
      (node (ref "D11") (pin "2") (pinfunction "DOUT_2") (pintype "output"))
      (node (ref "D12") (pin "4") (pinfunction "DIN_4") (pintype "input"))
    )
    (net (code "77") (name "Net-(D11-VSS)") (class "Default")
      (node (ref "D11") (pin "3") (pinfunction "VSS_3") (pintype "unspecified"))
      (node (ref "D12") (pin "1") (pinfunction "VDD_1") (pintype "unspecified"))
    )
    (net (code "78") (name "Net-(D12-DOUT)") (class "Default")
      (node (ref "D12") (pin "2") (pinfunction "DOUT_2") (pintype "output"))
      (node (ref "D13") (pin "4") (pinfunction "DIN_4") (pintype "input"))
    )
    (net (code "79") (name "Net-(D12-VSS)") (class "Default")
      (node (ref "C32") (pin "1") (pinfunction "~_1") (pintype "unspecified"))
      (node (ref "D12") (pin "3") (pinfunction "VSS_3") (pintype "unspecified"))
      (node (ref "D13") (pin "1") (pinfunction "VDD_1") (pintype "unspecified"))
    )
    (net (code "80") (name "Net-(D13-DOUT)") (class "Default")
      (node (ref "D13") (pin "2") (pinfunction "DOUT_2") (pintype "output"))
      (node (ref "D14") (pin "4") (pinfunction "DIN_4") (pintype "input"))
    )
    (net (code "81") (name "Net-(D13-VSS)") (class "Default")
      (node (ref "D13") (pin "3") (pinfunction "VSS_3") (pintype "unspecified"))
      (node (ref "D14") (pin "1") (pinfunction "VDD_1") (pintype "unspecified"))
    )
    (net (code "82") (name "Net-(D14-DOUT)") (class "Default")
      (node (ref "D14") (pin "2") (pinfunction "DOUT_2") (pintype "output"))
      (node (ref "D15") (pin "4") (pinfunction "DIN_4") (pintype "input"))
    )
    (net (code "83") (name "Net-(D14-VSS)") (class "Default")
      (node (ref "D14") (pin "3") (pinfunction "VSS_3") (pintype "unspecified"))
      (node (ref "D15") (pin "1") (pinfunction "VDD_1") (pintype "unspecified"))
    )
    (net (code "84") (name "Net-(D15-DOUT)") (class "Default")
      (node (ref "D15") (pin "2") (pinfunction "DOUT_2") (pintype "output"))
      (node (ref "D16") (pin "4") (pinfunction "DIN_4") (pintype "input"))
    )
    (net (code "85") (name "Net-(D15-VSS)") (class "Default")
      (node (ref "D15") (pin "3") (pinfunction "VSS_3") (pintype "unspecified"))
      (node (ref "D16") (pin "1") (pinfunction "VDD_1") (pintype "unspecified"))
    )
    (net (code "86") (name "Net-(D16-DOUT)") (class "Default")
      (node (ref "D16") (pin "2") (pinfunction "DOUT_2") (pintype "output"))
      (node (ref "D17") (pin "4") (pinfunction "DIN_4") (pintype "input"))
    )
    (net (code "87") (name "Net-(D16-VSS)") (class "Default")
      (node (ref "D16") (pin "3") (pinfunction "VSS_3") (pintype "unspecified"))
      (node (ref "D17") (pin "1") (pinfunction "VDD_1") (pintype "unspecified"))
    )
    (net (code "88") (name "Net-(D17-DOUT)") (class "Default")
      (node (ref "D17") (pin "2") (pinfunction "DOUT_2") (pintype "output"))
      (node (ref "D18") (pin "4") (pinfunction "DIN_4") (pintype "input"))
    )
    (net (code "89") (name "Net-(D17-VSS)") (class "Default")
      (node (ref "D17") (pin "3") (pinfunction "VSS_3") (pintype "unspecified"))
      (node (ref "D18") (pin "1") (pinfunction "VDD_1") (pintype "unspecified"))
    )
    (net (code "90") (name "Net-(D18-DOUT)") (class "Default")
      (node (ref "D18") (pin "2") (pinfunction "DOUT_2") (pintype "output"))
      (node (ref "D19") (pin "4") (pinfunction "DIN_4") (pintype "input"))
    )
    (net (code "91") (name "Net-(D18-VSS)") (class "Default")
      (node (ref "C33") (pin "1") (pinfunction "~_1") (pintype "unspecified"))
      (node (ref "D18") (pin "3") (pinfunction "VSS_3") (pintype "unspecified"))
      (node (ref "D19") (pin "1") (pinfunction "VDD_1") (pintype "unspecified"))
    )
    (net (code "92") (name "Net-(D19-DOUT)") (class "Default")
      (node (ref "D19") (pin "2") (pinfunction "DOUT_2") (pintype "output"))
      (node (ref "D20") (pin "4") (pinfunction "DIN_4") (pintype "input"))
    )
    (net (code "93") (name "Net-(D19-VSS)") (class "Default")
      (node (ref "D19") (pin "3") (pinfunction "VSS_3") (pintype "unspecified"))
      (node (ref "D20") (pin "1") (pinfunction "VDD_1") (pintype "unspecified"))
    )
    (net (code "94") (name "Net-(D20-DOUT)") (class "Default")
      (node (ref "D20") (pin "2") (pinfunction "DOUT_2") (pintype "output"))
      (node (ref "D21") (pin "4") (pinfunction "DIN_4") (pintype "input"))
    )
    (net (code "95") (name "Net-(D20-VSS)") (class "Default")
      (node (ref "D20") (pin "3") (pinfunction "VSS_3") (pintype "unspecified"))
      (node (ref "D21") (pin "1") (pinfunction "VDD_1") (pintype "unspecified"))
    )
    (net (code "96") (name "Net-(D21-DOUT)") (class "Default")
      (node (ref "D21") (pin "2") (pinfunction "DOUT_2") (pintype "output"))
      (node (ref "D22") (pin "4") (pinfunction "DIN_4") (pintype "input"))
    )
    (net (code "97") (name "Net-(D21-VSS)") (class "Default")
      (node (ref "D21") (pin "3") (pinfunction "VSS_3") (pintype "unspecified"))
      (node (ref "D22") (pin "1") (pinfunction "VDD_1") (pintype "unspecified"))
    )
    (net (code "98") (name "Net-(D22-DOUT)") (class "Default")
      (node (ref "D22") (pin "2") (pinfunction "DOUT_2") (pintype "output"))
      (node (ref "D23") (pin "4") (pinfunction "DIN_4") (pintype "input"))
    )
    (net (code "99") (name "Net-(D22-VSS)") (class "Default")
      (node (ref "D22") (pin "3") (pinfunction "VSS_3") (pintype "unspecified"))
      (node (ref "D23") (pin "1") (pinfunction "VDD_1") (pintype "unspecified"))
    )
    (net (code "100") (name "Net-(D23-DOUT)") (class "Default")
      (node (ref "D23") (pin "2") (pinfunction "DOUT_2") (pintype "output"))
      (node (ref "D24") (pin "4") (pinfunction "DIN_4") (pintype "input"))
    )
    (net (code "101") (name "Net-(D23-VSS)") (class "Default")
      (node (ref "D23") (pin "3") (pinfunction "VSS_3") (pintype "unspecified"))
      (node (ref "D24") (pin "1") (pinfunction "VDD_1") (pintype "unspecified"))
    )
    (net (code "102") (name "Net-(D24-DOUT)") (class "Default")
      (node (ref "D24") (pin "2") (pinfunction "DOUT_2") (pintype "output"))
      (node (ref "D25") (pin "4") (pinfunction "DIN_4") (pintype "input"))
    )
    (net (code "103") (name "Net-(D24-VSS)") (class "Default")
      (node (ref "C34") (pin "1") (pinfunction "~_1") (pintype "unspecified"))
      (node (ref "D24") (pin "3") (pinfunction "VSS_3") (pintype "unspecified"))
      (node (ref "D25") (pin "1") (pinfunction "VDD_1") (pintype "unspecified"))
    )
    (net (code "104") (name "Net-(D25-DOUT)") (class "Default")
      (node (ref "D25") (pin "2") (pinfunction "DOUT_2") (pintype "output"))
      (node (ref "D26") (pin "4") (pinfunction "DIN_4") (pintype "input"))
    )
    (net (code "105") (name "Net-(D25-VSS)") (class "Default")
      (node (ref "D25") (pin "3") (pinfunction "VSS_3") (pintype "unspecified"))
      (node (ref "D26") (pin "1") (pinfunction "VDD_1") (pintype "unspecified"))
    )
    (net (code "106") (name "Net-(D26-DOUT)") (class "Default")
      (node (ref "D26") (pin "2") (pinfunction "DOUT_2") (pintype "output"))
      (node (ref "D27") (pin "4") (pinfunction "DIN_4") (pintype "input"))
    )
    (net (code "107") (name "Net-(D26-VSS)") (class "Default")
      (node (ref "D26") (pin "3") (pinfunction "VSS_3") (pintype "unspecified"))
      (node (ref "D27") (pin "1") (pinfunction "VDD_1") (pintype "unspecified"))
    )
    (net (code "108") (name "Net-(D27-DOUT)") (class "Default")
      (node (ref "D27") (pin "2") (pinfunction "DOUT_2") (pintype "output"))
      (node (ref "D28") (pin "4") (pinfunction "DIN_4") (pintype "input"))
    )
    (net (code "109") (name "Net-(D27-VSS)") (class "Default")
      (node (ref "D27") (pin "3") (pinfunction "VSS_3") (pintype "unspecified"))
      (node (ref "D28") (pin "1") (pinfunction "VDD_1") (pintype "unspecified"))
    )
    (net (code "110") (name "Net-(D28-DOUT)") (class "Default")
      (node (ref "D28") (pin "2") (pinfunction "DOUT_2") (pintype "output"))
      (node (ref "D29") (pin "4") (pinfunction "DIN_4") (pintype "input"))
    )
    (net (code "111") (name "Net-(D28-VSS)") (class "Default")
      (node (ref "D28") (pin "3") (pinfunction "VSS_3") (pintype "unspecified"))
      (node (ref "D29") (pin "1") (pinfunction "VDD_1") (pintype "unspecified"))
    )
    (net (code "112") (name "Net-(D29-DOUT)") (class "Default")
      (node (ref "D29") (pin "2") (pinfunction "DOUT_2") (pintype "output"))
      (node (ref "D30") (pin "4") (pinfunction "DIN_4") (pintype "input"))
    )
    (net (code "113") (name "Net-(D29-VSS)") (class "Default")
      (node (ref "D29") (pin "3") (pinfunction "VSS_3") (pintype "unspecified"))
      (node (ref "D30") (pin "1") (pinfunction "VDD_1") (pintype "unspecified"))
    )
    (net (code "114") (name "Net-(D30-DOUT)") (class "Default")
      (node (ref "D30") (pin "2") (pinfunction "DOUT_2") (pintype "output"))
      (node (ref "D31") (pin "4") (pinfunction "DIN_4") (pintype "input"))
    )
    (net (code "115") (name "Net-(D30-VSS)") (class "Default")
      (node (ref "C35") (pin "1") (pinfunction "~_1") (pintype "unspecified"))
      (node (ref "D30") (pin "3") (pinfunction "VSS_3") (pintype "unspecified"))
      (node (ref "D31") (pin "1") (pinfunction "VDD_1") (pintype "unspecified"))
    )
    (net (code "116") (name "Net-(D31-DOUT)") (class "Default")
      (node (ref "D31") (pin "2") (pinfunction "DOUT_2") (pintype "output"))
      (node (ref "D32") (pin "4") (pinfunction "DIN_4") (pintype "input"))
    )
    (net (code "117") (name "Net-(D31-VSS)") (class "Default")
      (node (ref "D31") (pin "3") (pinfunction "VSS_3") (pintype "unspecified"))
      (node (ref "D32") (pin "1") (pinfunction "VDD_1") (pintype "unspecified"))
    )
    (net (code "118") (name "Net-(D32-DOUT)") (class "Default")
      (node (ref "D32") (pin "2") (pinfunction "DOUT_2") (pintype "output"))
      (node (ref "D33") (pin "4") (pinfunction "DIN_4") (pintype "input"))
    )
    (net (code "119") (name "Net-(D32-VSS)") (class "Default")
      (node (ref "D32") (pin "3") (pinfunction "VSS_3") (pintype "unspecified"))
      (node (ref "D33") (pin "1") (pinfunction "VDD_1") (pintype "unspecified"))
    )
    (net (code "120") (name "Net-(D33-DOUT)") (class "Default")
      (node (ref "D33") (pin "2") (pinfunction "DOUT_2") (pintype "output"))
      (node (ref "D34") (pin "4") (pinfunction "DIN_4") (pintype "input"))
    )
    (net (code "121") (name "Net-(D33-VSS)") (class "Default")
      (node (ref "D33") (pin "3") (pinfunction "VSS_3") (pintype "unspecified"))
      (node (ref "D34") (pin "1") (pinfunction "VDD_1") (pintype "unspecified"))
    )
    (net (code "122") (name "Net-(D34-DOUT)") (class "Default")
      (node (ref "D34") (pin "2") (pinfunction "DOUT_2") (pintype "output"))
      (node (ref "D35") (pin "4") (pinfunction "DIN_4") (pintype "input"))
    )
    (net (code "123") (name "Net-(D34-VSS)") (class "Default")
      (node (ref "D34") (pin "3") (pinfunction "VSS_3") (pintype "unspecified"))
      (node (ref "D35") (pin "1") (pinfunction "VDD_1") (pintype "unspecified"))
    )
    (net (code "124") (name "Net-(D35-DOUT)") (class "Default")
      (node (ref "D35") (pin "2") (pinfunction "DOUT_2") (pintype "output"))
      (node (ref "D36") (pin "4") (pinfunction "DIN_4") (pintype "input"))
    )
    (net (code "125") (name "Net-(D35-VSS)") (class "Default")
      (node (ref "D35") (pin "3") (pinfunction "VSS_3") (pintype "unspecified"))
      (node (ref "D36") (pin "1") (pinfunction "VDD_1") (pintype "unspecified"))
    )
    (net (code "126") (name "Net-(D36-DOUT)") (class "Default")
      (node (ref "D36") (pin "2") (pinfunction "DOUT_2") (pintype "output"))
      (node (ref "D37") (pin "4") (pinfunction "DIN_4") (pintype "input"))
    )
    (net (code "127") (name "Net-(D36-VSS)") (class "Default")
      (node (ref "C36") (pin "1") (pinfunction "~_1") (pintype "unspecified"))
      (node (ref "D36") (pin "3") (pinfunction "VSS_3") (pintype "unspecified"))
      (node (ref "D37") (pin "1") (pinfunction "VDD_1") (pintype "unspecified"))
    )
    (net (code "128") (name "Net-(D37-DOUT)") (class "Default")
      (node (ref "D37") (pin "2") (pinfunction "DOUT_2") (pintype "output"))
      (node (ref "D38") (pin "4") (pinfunction "DIN_4") (pintype "input"))
    )
    (net (code "129") (name "Net-(D37-VSS)") (class "Default")
      (node (ref "D37") (pin "3") (pinfunction "VSS_3") (pintype "unspecified"))
      (node (ref "D38") (pin "1") (pinfunction "VDD_1") (pintype "unspecified"))
    )
    (net (code "130") (name "Net-(D38-DOUT)") (class "Default")
      (node (ref "D38") (pin "2") (pinfunction "DOUT_2") (pintype "output"))
      (node (ref "D39") (pin "4") (pinfunction "DIN_4") (pintype "input"))
    )
    (net (code "131") (name "Net-(D38-VSS)") (class "Default")
      (node (ref "D38") (pin "3") (pinfunction "VSS_3") (pintype "unspecified"))
      (node (ref "D39") (pin "1") (pinfunction "VDD_1") (pintype "unspecified"))
    )
    (net (code "132") (name "Net-(D39-DOUT)") (class "Default")
      (node (ref "D39") (pin "2") (pinfunction "DOUT_2") (pintype "output"))
      (node (ref "D40") (pin "4") (pinfunction "DIN_4") (pintype "input"))
    )
    (net (code "133") (name "Net-(D39-VSS)") (class "Default")
      (node (ref "D39") (pin "3") (pinfunction "VSS_3") (pintype "unspecified"))
      (node (ref "D40") (pin "1") (pinfunction "VDD_1") (pintype "unspecified"))
    )
    (net (code "134") (name "Net-(D40-DOUT)") (class "Default")
      (node (ref "D40") (pin "2") (pinfunction "DOUT_2") (pintype "output"))
      (node (ref "D41") (pin "4") (pinfunction "DIN_4") (pintype "input"))
    )
    (net (code "135") (name "Net-(D40-VSS)") (class "Default")
      (node (ref "D40") (pin "3") (pinfunction "VSS_3") (pintype "unspecified"))
      (node (ref "D41") (pin "1") (pinfunction "VDD_1") (pintype "unspecified"))
    )
    (net (code "136") (name "Net-(D41-DOUT)") (class "Default")
      (node (ref "D41") (pin "2") (pinfunction "DOUT_2") (pintype "output"))
      (node (ref "D42") (pin "4") (pinfunction "DIN_4") (pintype "input"))
    )
    (net (code "137") (name "Net-(D41-VSS)") (class "Default")
      (node (ref "D41") (pin "3") (pinfunction "VSS_3") (pintype "unspecified"))
      (node (ref "D42") (pin "1") (pinfunction "VDD_1") (pintype "unspecified"))
    )
    (net (code "138") (name "Net-(D43-A)") (class "Default")
      (node (ref "D43") (pin "2") (pinfunction "A_2") (pintype "unspecified"))
      (node (ref "R21") (pin "1") (pinfunction "~_1") (pintype "unspecified"))
      (node (ref "U5") (pin "3") (pinfunction "C2_3") (pintype "unspecified"))
    )
    (net (code "139") (name "Net-(D43-K)") (class "Default")
      (node (ref "D43") (pin "1") (pinfunction "K_1") (pintype "unspecified"))
      (node (ref "J10") (pin "2") (pinfunction "2_2") (pintype "unspecified"))
      (node (ref "J2") (pin "4") (pinfunction "4_4") (pintype "unspecified"))
      (node (ref "U5") (pin "2") (pinfunction "C1_2") (pintype "unspecified"))
    )
    (net (code "140") (name "Net-(D45-A)") (class "Default")
      (node (ref "D45") (pin "2") (pinfunction "A_2") (pintype "unspecified"))
      (node (ref "R24") (pin "1") (pinfunction "~_1") (pintype "unspecified"))
      (node (ref "R25") (pin "1") (pinfunction "~_1") (pintype "unspecified"))
      (node (ref "U21") (pin "1") (pinfunction "OUTA_1") (pintype "output"))
    )
    (net (code "141") (name "Net-(D45-K)") (class "Default")
      (node (ref "D45") (pin "1") (pinfunction "K_1") (pintype "unspecified"))
      (node (ref "R23") (pin "1") (pinfunction "~_1") (pintype "unspecified"))
      (node (ref "U21") (pin "2") (pinfunction "INA-_2") (pintype "unspecified"))
    )
    (net (code "142") (name "Net-(D46-A)") (class "Default")
      (node (ref "D46") (pin "2") (pinfunction "A_2") (pintype "unspecified"))
      (node (ref "R50") (pin "1") (pinfunction "~_1") (pintype "unspecified"))
      (node (ref "R51") (pin "1") (pinfunction "~_1") (pintype "unspecified"))
      (node (ref "U22") (pin "7") (pinfunction "OUTB_7") (pintype "output"))
    )
    (net (code "143") (name "Net-(D46-K)") (class "Default")
      (node (ref "D46") (pin "1") (pinfunction "K_1") (pintype "unspecified"))
      (node (ref "R49") (pin "1") (pinfunction "~_1") (pintype "unspecified"))
      (node (ref "U22") (pin "6") (pinfunction "INB-_6") (pintype "unspecified"))
    )
    (net (code "144") (name "Net-(D47-A)") (class "Default")
      (node (ref "D47") (pin "2") (pinfunction "A_2") (pintype "unspecified"))
      (node (ref "R54") (pin "1") (pinfunction "~_1") (pintype "unspecified"))
      (node (ref "R55") (pin "1") (pinfunction "~_1") (pintype "unspecified"))
      (node (ref "U21") (pin "7") (pinfunction "OUTB_7") (pintype "output"))
    )
    (net (code "145") (name "Net-(D47-K)") (class "Default")
      (node (ref "D47") (pin "1") (pinfunction "K_1") (pintype "unspecified"))
      (node (ref "R53") (pin "1") (pinfunction "~_1") (pintype "unspecified"))
      (node (ref "U21") (pin "6") (pinfunction "INB-_6") (pintype "unspecified"))
    )
    (net (code "146") (name "Net-(D48-A)") (class "Default")
      (node (ref "D48") (pin "2") (pinfunction "A_2") (pintype "unspecified"))
      (node (ref "R58") (pin "1") (pinfunction "~_1") (pintype "unspecified"))
      (node (ref "R59") (pin "1") (pinfunction "~_1") (pintype "unspecified"))
      (node (ref "U22") (pin "1") (pinfunction "OUTA_1") (pintype "output"))
    )
    (net (code "147") (name "Net-(D48-K)") (class "Default")
      (node (ref "D48") (pin "1") (pinfunction "K_1") (pintype "unspecified"))
      (node (ref "R57") (pin "1") (pinfunction "~_1") (pintype "unspecified"))
      (node (ref "U22") (pin "2") (pinfunction "INA-_2") (pintype "unspecified"))
    )
    (net (code "148") (name "Net-(D49-A)") (class "Default")
      (node (ref "D49") (pin "2") (pinfunction "A_2") (pintype "unspecified"))
      (node (ref "R62") (pin "1") (pinfunction "~_1") (pintype "unspecified"))
      (node (ref "R63") (pin "1") (pinfunction "~_1") (pintype "unspecified"))
      (node (ref "U23") (pin "1") (pinfunction "OUTA_1") (pintype "output"))
    )
    (net (code "149") (name "Net-(D49-K)") (class "Default")
      (node (ref "D49") (pin "1") (pinfunction "K_1") (pintype "unspecified"))
      (node (ref "R61") (pin "1") (pinfunction "~_1") (pintype "unspecified"))
      (node (ref "U23") (pin "2") (pinfunction "INA-_2") (pintype "unspecified"))
    )
    (net (code "150") (name "Net-(D50-A)") (class "Default")
      (node (ref "D50") (pin "2") (pinfunction "A_2") (pintype "unspecified"))
      (node (ref "R66") (pin "1") (pinfunction "~_1") (pintype "unspecified"))
      (node (ref "R67") (pin "1") (pinfunction "~_1") (pintype "unspecified"))
      (node (ref "U23") (pin "7") (pinfunction "OUTB_7") (pintype "output"))
    )
    (net (code "151") (name "Net-(D50-K)") (class "Default")
      (node (ref "D50") (pin "1") (pinfunction "K_1") (pintype "unspecified"))
      (node (ref "R65") (pin "1") (pinfunction "~_1") (pintype "unspecified"))
      (node (ref "U23") (pin "6") (pinfunction "INB-_6") (pintype "unspecified"))
    )
    (net (code "152") (name "Net-(D51-DOUT)") (class "Default")
      (node (ref "D51") (pin "2") (pinfunction "DOUT_2") (pintype "output"))
      (node (ref "D52") (pin "4") (pinfunction "DIN_4") (pintype "input"))
    )
    (net (code "153") (name "Net-(D51-VSS)") (class "Default")
      (node (ref "D51") (pin "3") (pinfunction "VSS_3") (pintype "unspecified"))
      (node (ref "D52") (pin "1") (pinfunction "VDD_1") (pintype "unspecified"))
    )
    (net (code "154") (name "Net-(D52-DOUT)") (class "Default")
      (node (ref "D52") (pin "2") (pinfunction "DOUT_2") (pintype "output"))
      (node (ref "D53") (pin "4") (pinfunction "DIN_4") (pintype "input"))
    )
    (net (code "155") (name "Net-(D52-VSS)") (class "Default")
      (node (ref "D52") (pin "3") (pinfunction "VSS_3") (pintype "unspecified"))
      (node (ref "D53") (pin "1") (pinfunction "VDD_1") (pintype "unspecified"))
    )
    (net (code "156") (name "Net-(D53-DOUT)") (class "Default")
      (node (ref "D53") (pin "2") (pinfunction "DOUT_2") (pintype "output"))
      (node (ref "D54") (pin "4") (pinfunction "DIN_4") (pintype "input"))
    )
    (net (code "157") (name "Net-(D53-VSS)") (class "Default")
      (node (ref "D53") (pin "3") (pinfunction "VSS_3") (pintype "unspecified"))
      (node (ref "D54") (pin "1") (pinfunction "VDD_1") (pintype "unspecified"))
    )
    (net (code "158") (name "Net-(D54-DOUT)") (class "Default")
      (node (ref "D54") (pin "2") (pinfunction "DOUT_2") (pintype "output"))
      (node (ref "D55") (pin "4") (pinfunction "DIN_4") (pintype "input"))
    )
    (net (code "159") (name "Net-(D54-VSS)") (class "Default")
      (node (ref "D54") (pin "3") (pinfunction "VSS_3") (pintype "unspecified"))
      (node (ref "D55") (pin "1") (pinfunction "VDD_1") (pintype "unspecified"))
    )
    (net (code "160") (name "Net-(D55-DOUT)") (class "Default")
      (node (ref "D55") (pin "2") (pinfunction "DOUT_2") (pintype "output"))
      (node (ref "D56") (pin "4") (pinfunction "DIN_4") (pintype "input"))
    )
    (net (code "161") (name "Net-(D55-VSS)") (class "Default")
      (node (ref "D55") (pin "3") (pinfunction "VSS_3") (pintype "unspecified"))
      (node (ref "D56") (pin "1") (pinfunction "VDD_1") (pintype "unspecified"))
    )
    (net (code "162") (name "Net-(D56-DOUT)") (class "Default")
      (node (ref "D56") (pin "2") (pinfunction "DOUT_2") (pintype "output"))
      (node (ref "D57") (pin "4") (pinfunction "DIN_4") (pintype "input"))
    )
    (net (code "163") (name "Net-(D57-DOUT)") (class "Default")
      (node (ref "D57") (pin "2") (pinfunction "DOUT_2") (pintype "output"))
      (node (ref "D60") (pin "4") (pinfunction "DIN_4") (pintype "input"))
    )
    (net (code "164") (name "Net-(D57-VSS)") (class "Default")
      (node (ref "D57") (pin "3") (pinfunction "VSS_3") (pintype "unspecified"))
      (node (ref "D60") (pin "1") (pinfunction "VDD_1") (pintype "unspecified"))
    )
    (net (code "165") (name "Net-(D58-DIN)") (class "Default")
      (node (ref "D58") (pin "4") (pinfunction "DIN_4") (pintype "input"))
      (node (ref "D59") (pin "2") (pinfunction "DOUT_2") (pintype "output"))
    )
    (net (code "166") (name "Net-(D58-VDD)") (class "Default")
      (node (ref "D58") (pin "1") (pinfunction "VDD_1") (pintype "unspecified"))
      (node (ref "D59") (pin "3") (pinfunction "VSS_3") (pintype "unspecified"))
    )
    (net (code "167") (name "Net-(D59-DIN)") (class "Default")
      (node (ref "D59") (pin "4") (pinfunction "DIN_4") (pintype "input"))
      (node (ref "D60") (pin "2") (pinfunction "DOUT_2") (pintype "output"))
    )
    (net (code "168") (name "Net-(D59-VDD)") (class "Default")
      (node (ref "D59") (pin "1") (pinfunction "VDD_1") (pintype "unspecified"))
      (node (ref "D60") (pin "3") (pinfunction "VSS_3") (pintype "unspecified"))
    )
    (net (code "169") (name "Net-(J3-Pad4)") (class "Default")
      (node (ref "J3") (pin "4") (pinfunction "4_4") (pintype "unspecified"))
      (node (ref "R4") (pin "1") (pinfunction "~_1") (pintype "unspecified"))
    )
    (net (code "170") (name "Net-(J3-Pad5)") (class "Default")
      (node (ref "J3") (pin "5") (pinfunction "5_5") (pintype "unspecified"))
      (node (ref "R19") (pin "1") (pinfunction "~_1") (pintype "unspecified"))
    )
    (net (code "171") (name "Net-(J10-Pad4)") (class "Default")
      (node (ref "J10") (pin "4") (pinfunction "4_4") (pintype "unspecified"))
      (node (ref "J2") (pin "5") (pinfunction "5_5") (pintype "unspecified"))
      (node (ref "R21") (pin "2") (pinfunction "~_2") (pintype "unspecified"))
    )
    (net (code "172") (name "Net-(J11-Pad2)") (class "Default")
      (node (ref "J11") (pin "2") (pinfunction "2_2") (pintype "unspecified"))
      (node (ref "R70") (pin "1") (pinfunction "~_1") (pintype "unspecified"))
    )
    (net (code "173") (name "Net-(J11-Pad4)") (class "Default")
      (node (ref "J11") (pin "4") (pinfunction "4_4") (pintype "unspecified"))
      (node (ref "R71") (pin "1") (pinfunction "~_1") (pintype "unspecified"))
    )
    (net (code "174") (name "Net-(LEDPWR1-A)") (class "Default")
      (node (ref "LEDPWR1") (pin "2") (pinfunction "A_2") (pintype "input"))
      (node (ref "U1") (pin "23") (pinfunction "23_23") (pintype "bidirectional"))
    )
    (net (code "175") (name "Net-(U8-1Y)") (class "Default")
      (node (ref "R20") (pin "1") (pinfunction "~_1") (pintype "unspecified"))
      (node (ref "U8") (pin "3") (pinfunction "1Y_3") (pintype "unspecified"))
    )
    (net (code "176") (name "Net-(U21A-VSS)") (class "Default")
      (node (ref "C25") (pin "1") (pinfunction "1_1") (pintype "unspecified"))
      (node (ref "U21") (pin "4") (pinfunction "VSS_4") (pintype "unspecified"))
    )
    (net (code "177") (name "Net-(U22A-VDD)") (class "Default")
      (node (ref "C47") (pin "2") (pinfunction "2_2") (pintype "unspecified"))
      (node (ref "U22") (pin "8") (pinfunction "VDD_8") (pintype "unspecified"))
    )
    (net (code "178") (name "Net-(U22A-VSS)") (class "Default")
      (node (ref "C47") (pin "1") (pinfunction "1_1") (pintype "unspecified"))
      (node (ref "U22") (pin "4") (pinfunction "VSS_4") (pintype "unspecified"))
    )
    (net (code "179") (name "Net-(U23A-VDD)") (class "Default")
      (node (ref "C50") (pin "2") (pinfunction "2_2") (pintype "unspecified"))
      (node (ref "U23") (pin "8") (pinfunction "VDD_8") (pintype "unspecified"))
    )
    (net (code "180") (name "Net-(U23A-VSS)") (class "Default")
      (node (ref "C50") (pin "1") (pinfunction "1_1") (pintype "unspecified"))
      (node (ref "U23") (pin "4") (pinfunction "VSS_4") (pintype "unspecified"))
    )
    (net (code "181") (name "ROW1") (class "Default")
      (node (ref "ROW_MUX1") (pin "9") (pinfunction "I0_9") (pintype "unspecified"))
      (node (ref "SW1") (pin "1") (pinfunction "1_1") (pintype "unspecified"))
      (node (ref "SW15") (pin "1") (pinfunction "1_1") (pintype "unspecified"))
      (node (ref "SW22") (pin "1") (pinfunction "1_1") (pintype "unspecified"))
      (node (ref "SW29") (pin "1") (pinfunction "1_1") (pintype "unspecified"))
      (node (ref "SW36") (pin "1") (pinfunction "1_1") (pintype "unspecified"))
      (node (ref "SW8") (pin "1") (pinfunction "1_1") (pintype "unspecified"))
    )
    (net (code "182") (name "ROW2") (class "Default")
      (node (ref "ROW_MUX1") (pin "8") (pinfunction "I1_8") (pintype "unspecified"))
      (node (ref "SW16") (pin "1") (pinfunction "1_1") (pintype "unspecified"))
      (node (ref "SW2") (pin "1") (pinfunction "1_1") (pintype "unspecified"))
      (node (ref "SW23") (pin "1") (pinfunction "1_1") (pintype "unspecified"))
      (node (ref "SW30") (pin "1") (pinfunction "1_1") (pintype "unspecified"))
      (node (ref "SW37") (pin "1") (pinfunction "1_1") (pintype "unspecified"))
      (node (ref "SW9") (pin "1") (pinfunction "1_1") (pintype "unspecified"))
    )
    (net (code "183") (name "ROW3") (class "Default")
      (node (ref "ROW_MUX1") (pin "7") (pinfunction "I2_7") (pintype "unspecified"))
      (node (ref "SW10") (pin "1") (pinfunction "1_1") (pintype "unspecified"))
      (node (ref "SW17") (pin "1") (pinfunction "1_1") (pintype "unspecified"))
      (node (ref "SW24") (pin "1") (pinfunction "1_1") (pintype "unspecified"))
      (node (ref "SW3") (pin "1") (pinfunction "1_1") (pintype "unspecified"))
      (node (ref "SW31") (pin "1") (pinfunction "1_1") (pintype "unspecified"))
      (node (ref "SW38") (pin "1") (pinfunction "1_1") (pintype "unspecified"))
    )
    (net (code "184") (name "ROW4") (class "Default")
      (node (ref "ROW_MUX1") (pin "6") (pinfunction "I3_6") (pintype "unspecified"))
      (node (ref "SW11") (pin "1") (pinfunction "1_1") (pintype "unspecified"))
      (node (ref "SW18") (pin "1") (pinfunction "1_1") (pintype "unspecified"))
      (node (ref "SW25") (pin "1") (pinfunction "1_1") (pintype "unspecified"))
      (node (ref "SW32") (pin "1") (pinfunction "1_1") (pintype "unspecified"))
      (node (ref "SW39") (pin "1") (pinfunction "1_1") (pintype "unspecified"))
      (node (ref "SW4") (pin "1") (pinfunction "1_1") (pintype "unspecified"))
    )
    (net (code "185") (name "ROW5") (class "Default")
      (node (ref "ROW_MUX1") (pin "4") (pinfunction "I5_4") (pintype "unspecified"))
      (node (ref "ROW_MUX1") (pin "5") (pinfunction "I4_5") (pintype "unspecified"))
      (node (ref "SW12") (pin "1") (pinfunction "1_1") (pintype "unspecified"))
      (node (ref "SW19") (pin "1") (pinfunction "1_1") (pintype "unspecified"))
      (node (ref "SW26") (pin "1") (pinfunction "1_1") (pintype "unspecified"))
      (node (ref "SW33") (pin "1") (pinfunction "1_1") (pintype "unspecified"))
      (node (ref "SW40") (pin "1") (pinfunction "1_1") (pintype "unspecified"))
      (node (ref "SW5") (pin "1") (pinfunction "1_1") (pintype "unspecified"))
    )
    (net (code "186") (name "ROW6") (class "Default")
      (node (ref "ROW_MUX1") (pin "3") (pinfunction "I6_3") (pintype "unspecified"))
      (node (ref "SW13") (pin "1") (pinfunction "1_1") (pintype "unspecified"))
      (node (ref "SW20") (pin "1") (pinfunction "1_1") (pintype "unspecified"))
      (node (ref "SW27") (pin "1") (pinfunction "1_1") (pintype "unspecified"))
      (node (ref "SW34") (pin "1") (pinfunction "1_1") (pintype "unspecified"))
      (node (ref "SW41") (pin "1") (pinfunction "1_1") (pintype "unspecified"))
      (node (ref "SW6") (pin "1") (pinfunction "1_1") (pintype "unspecified"))
    )
    (net (code "187") (name "ROW7") (class "Default")
      (node (ref "ROW_MUX1") (pin "2") (pinfunction "I7_2") (pintype "unspecified"))
      (node (ref "SW14") (pin "1") (pinfunction "1_1") (pintype "unspecified"))
      (node (ref "SW21") (pin "1") (pinfunction "1_1") (pintype "unspecified"))
      (node (ref "SW28") (pin "1") (pinfunction "1_1") (pintype "unspecified"))
      (node (ref "SW35") (pin "1") (pinfunction "1_1") (pintype "unspecified"))
      (node (ref "SW42") (pin "1") (pinfunction "1_1") (pintype "unspecified"))
      (node (ref "SW7") (pin "1") (pinfunction "1_1") (pintype "unspecified"))
    )
    (net (code "188") (name "SCL") (class "Default")
      (node (ref "R68") (pin "1") (pinfunction "~_1") (pintype "unspecified"))
      (node (ref "R69") (pin "2") (pinfunction "~_2") (pintype "unspecified"))
      (node (ref "Screen1") (pin "3") (pinfunction "Pin_3_3") (pintype "unspecified"))
      (node (ref "U1") (pin "19") (pinfunction "19_19") (pintype "bidirectional"))
    )
    (net (code "189") (name "SDA") (class "Default")
      (node (ref "R68") (pin "2") (pinfunction "~_2") (pintype "unspecified"))
      (node (ref "Screen1") (pin "4") (pinfunction "Pin_4_4") (pintype "unspecified"))
      (node (ref "U1") (pin "18") (pinfunction "18_18") (pintype "bidirectional"))
    )
    (net (code "190") (name "TPWR") (class "Default")
      (node (ref "SW49") (pin "2") (pinfunction "2_2") (pintype "unspecified"))
      (node (ref "U1") (pin "VIN") (pinfunction "VIN_VIN") (pintype "unspecified"))
    )
    (net (code "191") (name "VIN_FUSED") (class "Default")
      (node (ref "C5") (pin "2") (pinfunction "2_2") (pintype "input"))
      (node (ref "C6") (pin "2") (pinfunction "2_2") (pintype "unspecified"))
      (node (ref "D44") (pin "1") (pinfunction "K_1") (pintype "input"))
      (node (ref "F1") (pin "2") (pinfunction "2_2") (pintype "unspecified"))
      (node (ref "SW49") (pin "4") (pinfunction "4_4") (pintype "unspecified"))
      (node (ref "SW49") (pin "6") (pinfunction "6_6") (pintype "unspecified"))
      (node (ref "U6") (pin "1") (pinfunction "1_1") (pintype "unspecified"))
    )
    (net (code "192") (name "VIN_RAW") (class "Default")
      (node (ref "F1") (pin "1") (pinfunction "1_1") (pintype "unspecified"))
      (node (ref "J1") (pin "1") (pinfunction "1_1") (pintype "unspecified"))
    )
    (net (code "193") (name "VLED") (class "Default")
      (node (ref "C2") (pin "1") (pinfunction "~_1") (pintype "unspecified"))
      (node (ref "C59") (pin "1") (pinfunction "~_1") (pintype "unspecified"))
      (node (ref "C7") (pin "2") (pinfunction "2_2") (pintype "unspecified"))
      (node (ref "D1") (pin "1") (pinfunction "VDD_1") (pintype "unspecified"))
      (node (ref "D57") (pin "1") (pinfunction "VDD_1") (pintype "unspecified"))
      (node (ref "U6") (pin "2") (pinfunction "2_2") (pintype "unspecified"))
    )
    (net (code "194") (name "VREF") (class "Default")
      (node (ref "R46") (pin "2") (pinfunction "~_2") (pintype "unspecified"))
      (node (ref "R47") (pin "2") (pinfunction "~_2") (pintype "unspecified"))
      (node (ref "U21") (pin "3") (pinfunction "INA+_3") (pintype "unspecified"))
      (node (ref "U21") (pin "5") (pinfunction "INB+_5") (pintype "unspecified"))
      (node (ref "U22") (pin "3") (pinfunction "INA+_3") (pintype "unspecified"))
      (node (ref "U22") (pin "5") (pinfunction "INB+_5") (pintype "unspecified"))
      (node (ref "U23") (pin "3") (pinfunction "INA+_3") (pintype "unspecified"))
      (node (ref "U23") (pin "5") (pinfunction "INB+_5") (pintype "unspecified"))
    )
    (net (code "195") (name "unconnected-(J2-Pad1)") (class "Default")
      (node (ref "J2") (pin "1") (pinfunction "1_1") (pintype "unspecified"))
    )
    (net (code "196") (name "unconnected-(J2-Pad3)") (class "Default")
      (node (ref "J2") (pin "3") (pinfunction "3_3") (pintype "unspecified+no_connect"))
    )
    (net (code "197") (name "unconnected-(J2-Pad6)") (class "Default")
      (node (ref "J2") (pin "6") (pinfunction "6_6") (pintype "unspecified+no_connect"))
    )
    (net (code "198") (name "unconnected-(J2-Pad7)") (class "Default")
      (node (ref "J2") (pin "7") (pinfunction "7_7") (pintype "unspecified+no_connect"))
    )
    (net (code "199") (name "unconnected-(J3-Pad1)") (class "Default")
      (node (ref "J3") (pin "1") (pinfunction "1_1") (pintype "unspecified+no_connect"))
    )
    (net (code "200") (name "unconnected-(J3-Pad3)") (class "Default")
      (node (ref "J3") (pin "3") (pinfunction "3_3") (pintype "unspecified+no_connect"))
    )
    (net (code "201") (name "unconnected-(J3-Pad6)") (class "Default")
      (node (ref "J3") (pin "6") (pinfunction "6_6") (pintype "unspecified+no_connect"))
    )
    (net (code "202") (name "unconnected-(J3-Pad7)") (class "Default")
      (node (ref "J3") (pin "7") (pinfunction "7_7") (pintype "unspecified+no_connect"))
    )
    (net (code "203") (name "unconnected-(U1-ON{slash}OFF-PadON-OFF)") (class "Default")
      (node (ref "U1") (pin "ON-OFF") (pinfunction "ON/OFF_ON-OFF") (pintype "bidirectional+no_connect"))
    )
    (net (code "204") (name "unconnected-(U1-PROGRAM-PadPGM)") (class "Default")
      (node (ref "U1") (pin "PGM") (pinfunction "PROGRAM_PGM") (pintype "bidirectional+no_connect"))
    )
    (net (code "205") (name "unconnected-(U1-Pad12)") (class "Default")
      (node (ref "U1") (pin "12") (pinfunction "12_12") (pintype "bidirectional+no_connect"))
    )
    (net (code "206") (name "unconnected-(U1-Pad13)") (class "Default")
      (node (ref "U1") (pin "13") (pinfunction "13_13") (pintype "bidirectional+no_connect"))
    )
    (net (code "207") (name "unconnected-(U1-PadVBAT)") (class "Default")
      (node (ref "U1") (pin "VBAT") (pinfunction "VBAT_VBAT") (pintype "unspecified+no_connect"))
    )
    (net (code "208") (name "unconnected-(U5-NC-Pad1)") (class "Default")
      (node (ref "U5") (pin "1") (pinfunction "NC_1") (pintype "unspecified+no_connect"))
    )
    (net (code "209") (name "unconnected-(U5-NC-Pad4)") (class "Default")
      (node (ref "U5") (pin "4") (pinfunction "NC_4") (pintype "unspecified+no_connect"))
    )
  )
)
